# Motherboard_STM32F405RG.net
KiCad netlist of a schematic drawn in EAGLE
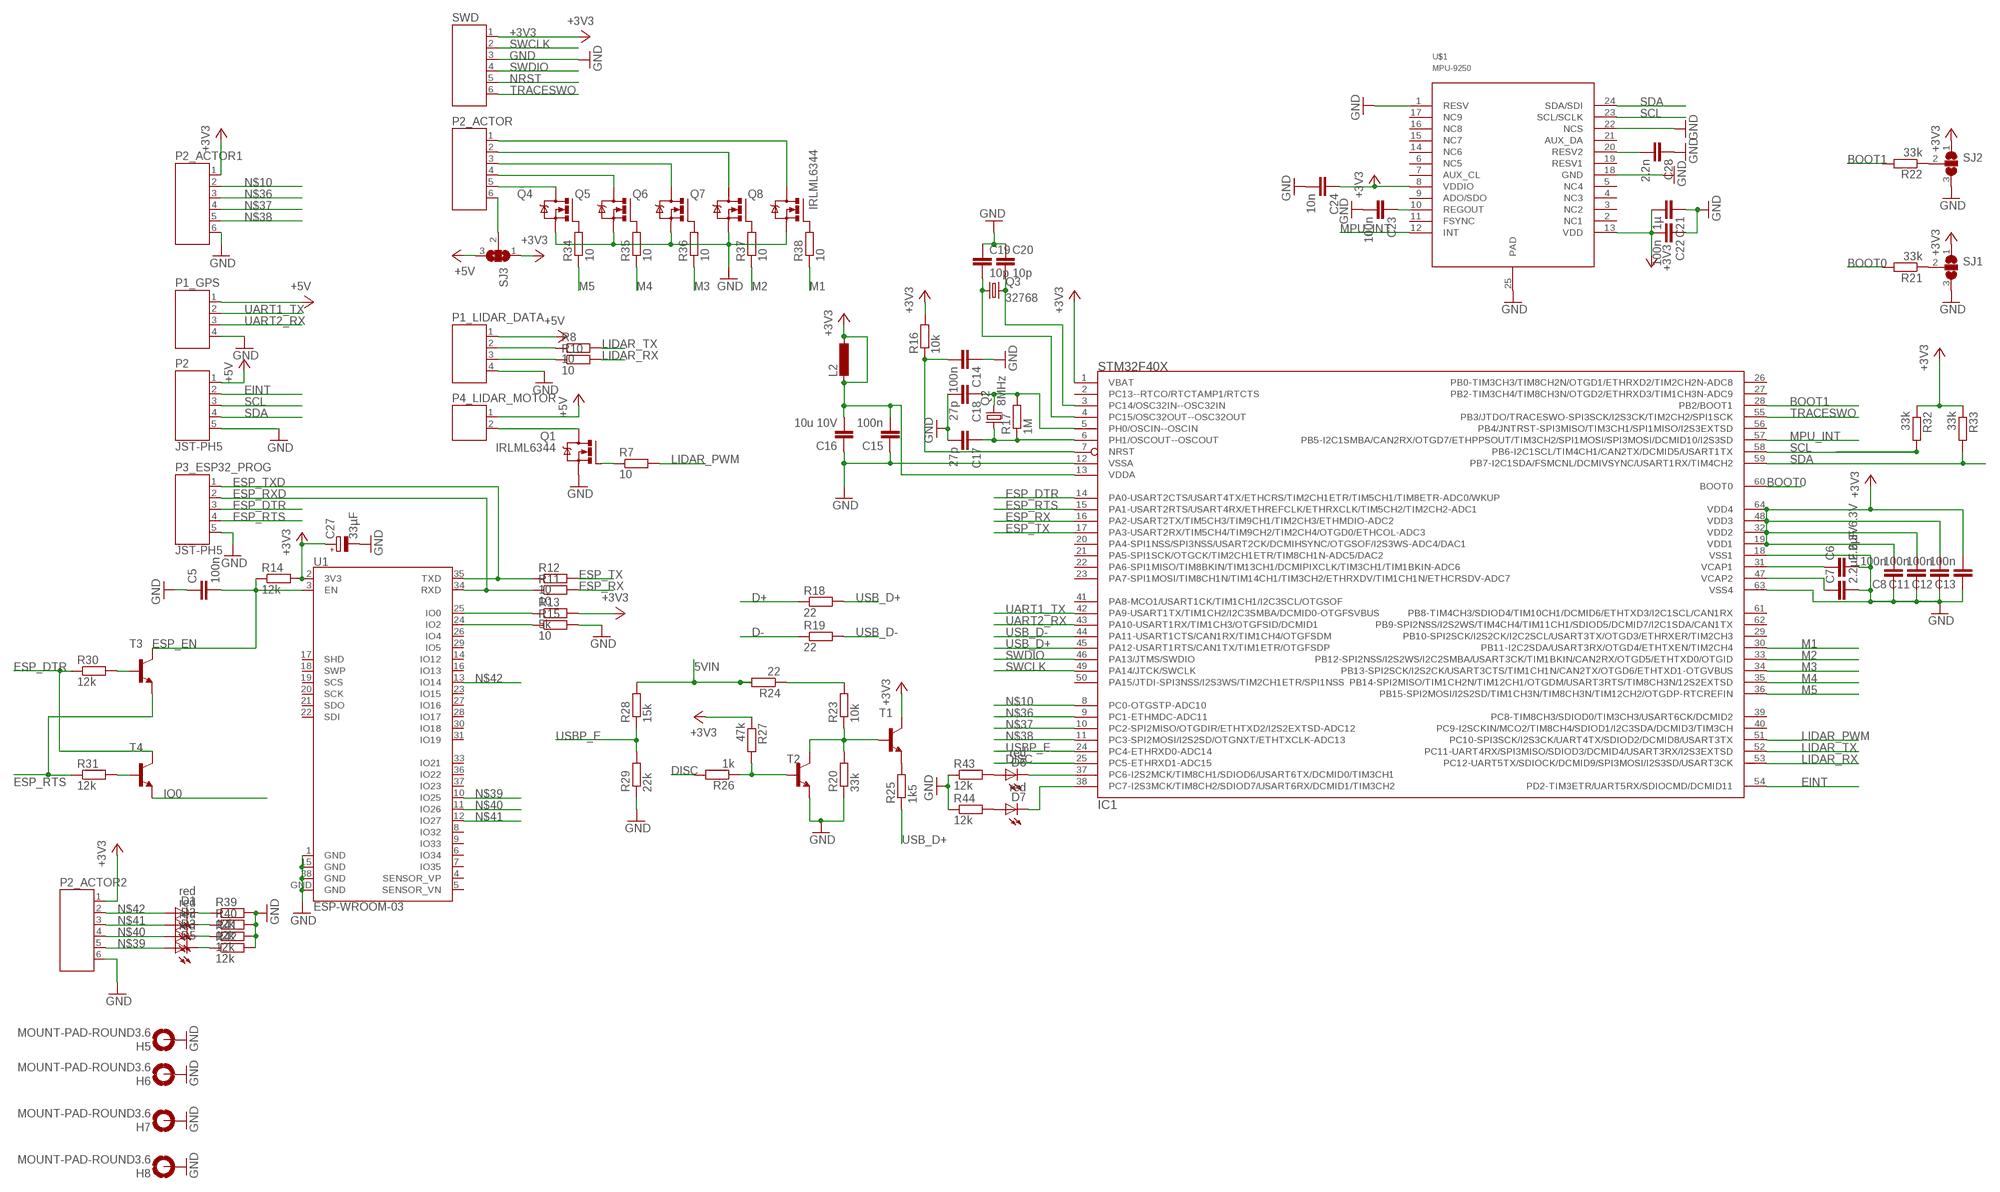
[diagram p0: schematic, sheet 1]
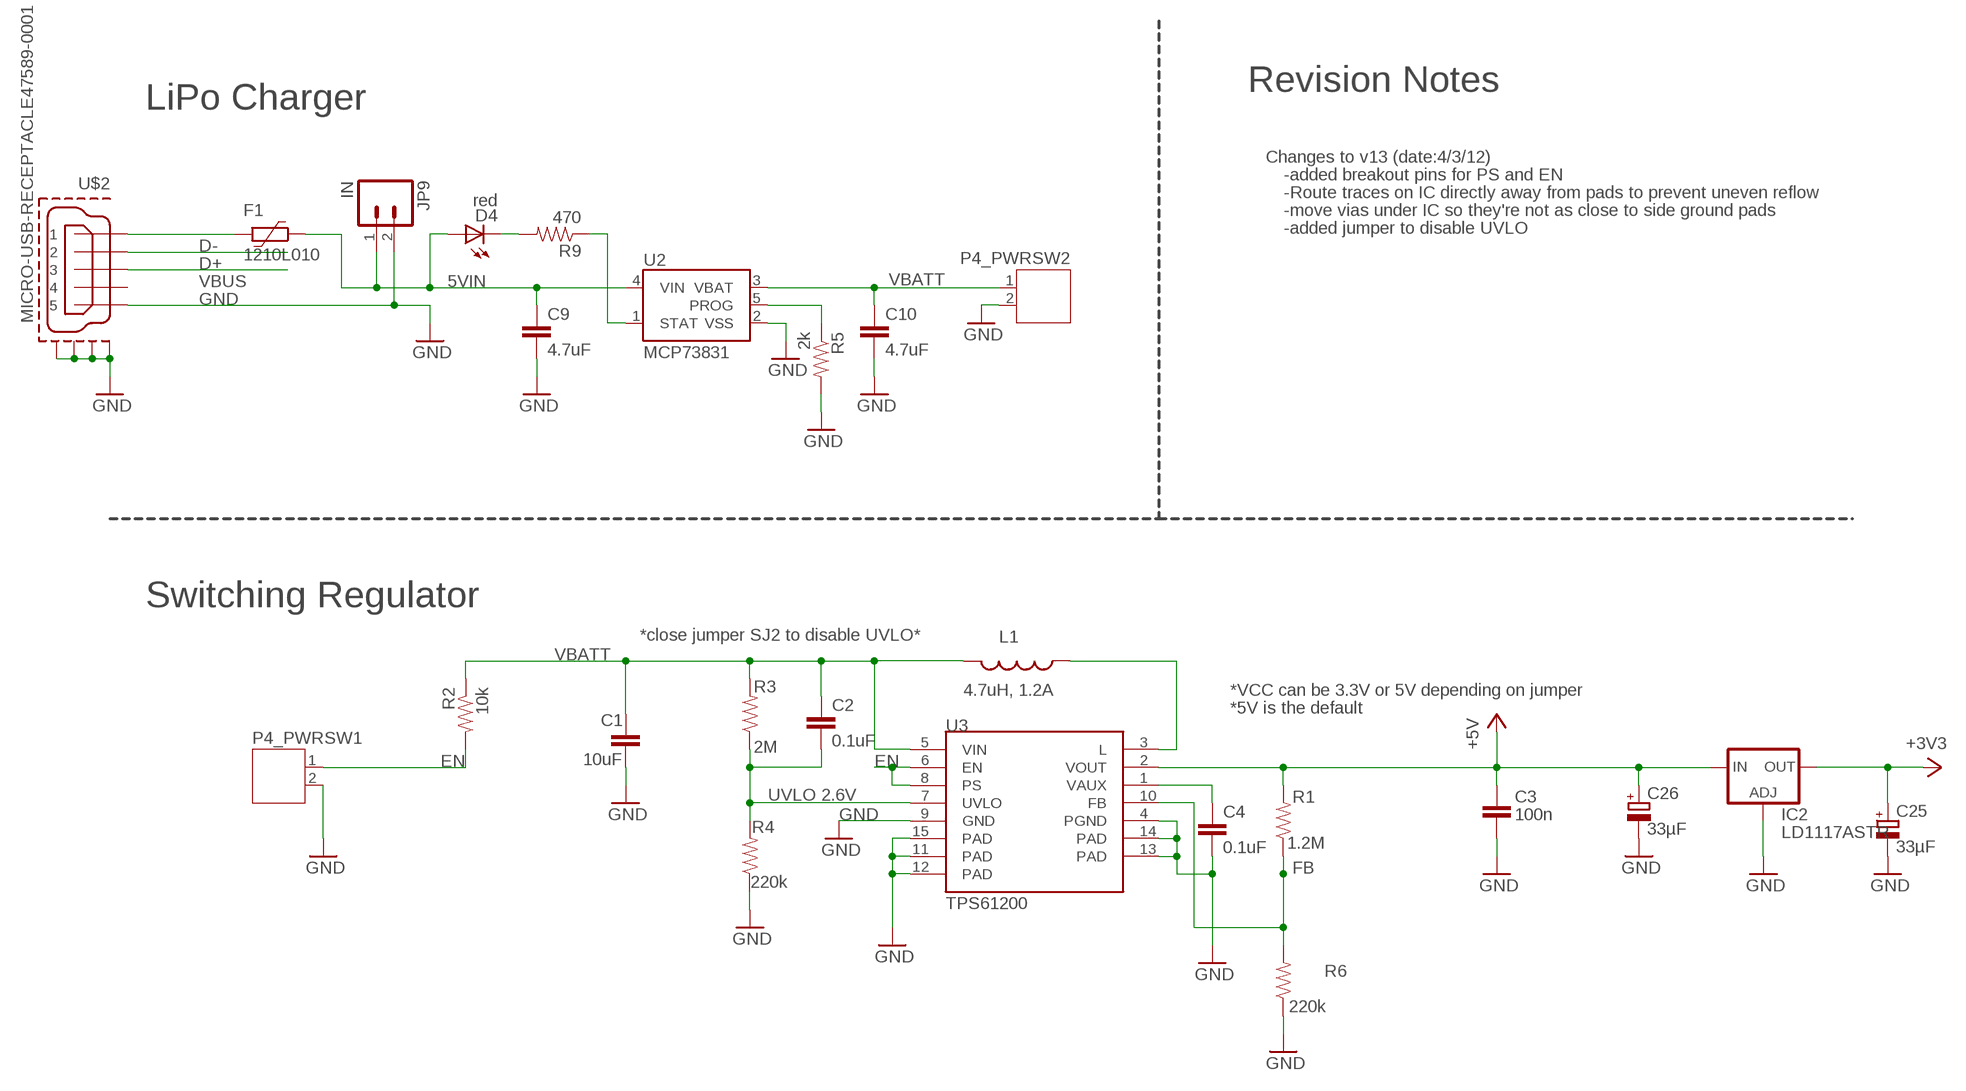
[diagram p1: schematic, sheet 2]

(export (version "E")
  (design (tool "Eeschema 10.0.6"))
  (components
    (comp (ref "C5")
      (value "100n")
      (footprint "eagle-import:C0603")
      (fields (field (name "MF") "KEMET") (field (name "MPN") "C0603C104K5RACTU"))
      (libsource (lib "eagle-import") (part "C-EUC0603"))
    )
    (comp (ref "C6")
      (value "2.2µF 6.3V")
      (footprint "eagle-import:C0603")
      (fields (field (name "MF") "KEMET") (field (name "MPN") "C0603C225K9PACTU"))
      (libsource (lib "eagle-import") (part "C-EUC0603"))
    )
    (comp (ref "C7")
      (value "2.2µF 6.3V")
      (footprint "eagle-import:C0603")
      (fields (field (name "MF") "KEMET") (field (name "MPN") "C0603C225K9PACTU"))
      (libsource (lib "eagle-import") (part "C-EUC0603"))
    )
    (comp (ref "C8")
      (value "100n")
      (footprint "eagle-import:C0603")
      (fields (field (name "MF") "KEMET") (field (name "MPN") "C0603C104K5RACTU"))
      (libsource (lib "eagle-import") (part "C-EUC0603"))
    )
    (comp (ref "C11")
      (value "100n")
      (footprint "eagle-import:C0603")
      (fields (field (name "MF") "KEMET") (field (name "MPN") "C0603C104K5RACTU"))
      (libsource (lib "eagle-import") (part "C-EUC0603"))
    )
    (comp (ref "C12")
      (value "100n")
      (footprint "eagle-import:C0603")
      (fields (field (name "MF") "KEMET") (field (name "MPN") "C0603C104K5RACTU"))
      (libsource (lib "eagle-import") (part "C-EUC0603"))
    )
    (comp (ref "C13")
      (value "100n")
      (footprint "eagle-import:C0603")
      (fields (field (name "MF") "KEMET") (field (name "MPN") "C0603C104K5RACTU"))
      (libsource (lib "eagle-import") (part "C-EUC0603"))
    )
    (comp (ref "C14")
      (value "100n")
      (footprint "eagle-import:C0603")
      (fields (field (name "MF") "KEMET") (field (name "MPN") "C0603C104K5RACTU"))
      (libsource (lib "eagle-import") (part "C-EUC0603"))
    )
    (comp (ref "C15")
      (value "100n")
      (footprint "eagle-import:C0603")
      (fields (field (name "MF") "KEMET") (field (name "MPN") "C0603C104K5RACTU"))
      (libsource (lib "eagle-import") (part "C-EUC0603"))
    )
    (comp (ref "C16")
      (value "10u 10V")
      (footprint "eagle-import:C1206")
      (fields (field (name "MF") "KEMET") (field (name "MPN") "C1206C106K8RACTU"))
      (libsource (lib "eagle-import") (part "C-EUC1206"))
    )
    (comp (ref "C17")
      (value "27p")
      (footprint "eagle-import:C0603")
      (fields (field (name "MF") "YAGEO (PHYCOMP)") (field (name "MPN") "CC0603JRNPO9BN270"))
      (libsource (lib "eagle-import") (part "C-EUC0603"))
    )
    (comp (ref "C18")
      (value "27p")
      (footprint "eagle-import:C0603")
      (fields (field (name "MF") "YAGEO (PHYCOMP)") (field (name "MPN") "CC0603JRNPO9BN270"))
      (libsource (lib "eagle-import") (part "C-EUC0603"))
    )
    (comp (ref "C19")
      (value "10p")
      (footprint "eagle-import:C0603")
      (fields (field (name "MF") "AVX") (field (name "MPN") "06035A102JAT2A"))
      (libsource (lib "eagle-import") (part "C-EUC0603"))
    )
    (comp (ref "C20")
      (value "10p")
      (footprint "eagle-import:C0603")
      (fields (field (name "MF") "AVX") (field (name "MPN") "06035A102JAT2A"))
      (libsource (lib "eagle-import") (part "C-EUC0603"))
    )
    (comp (ref "C21")
      (value "1µ")
      (footprint "eagle-import:C0603")
      (fields (field (name "MF") "AVX") (field (name "MPN") "0603YC105KAT2A"))
      (libsource (lib "eagle-import") (part "C-EUC0603"))
    )
    (comp (ref "C22")
      (value "100n")
      (footprint "eagle-import:C0603")
      (fields (field (name "MF") "KEMET") (field (name "MPN") "C0603C104K5RACTU"))
      (libsource (lib "eagle-import") (part "C-EUC0603"))
    )
    (comp (ref "C23")
      (value "100n")
      (footprint "eagle-import:C0603")
      (fields (field (name "MF") "KEMET") (field (name "MPN") "C0603C104K5RACTU"))
      (libsource (lib "eagle-import") (part "C-EUC0603"))
    )
    (comp (ref "C24")
      (value "10n")
      (footprint "eagle-import:C0603")
      (fields (field (name "MF") "YAGEO (PHYCOMP)") (field (name "MPN") "CC0603KRX7R9BB103"))
      (libsource (lib "eagle-import") (part "C-EUC0603"))
    )
    (comp (ref "C27")
      (value "33µF")
      (footprint "eagle-import:A_3216-18W")
      (fields (field (name "MF") "AVX") (field (name "MPN") "TPSA336M006R0600"))
      (libsource (lib "eagle-import") (part "CPOL-EUA/3216-18W"))
    )
    (comp (ref "C28")
      (value "2.2n")
      (footprint "eagle-import:C0603")
      (fields (field (name "MF") "YAGEO (PHYCOMP)") (field (name "MPN") "CC0603KRX7R9BB222"))
      (libsource (lib "eagle-import") (part "C-EUC0603"))
    )
    (comp (ref "D1")
      (value "red")
      (footprint "eagle-import:LED-0603")
      (fields (field (name "MF") "OSRAM") (field (name "MPN") "LSQ976-Z"))
      (libsource (lib "eagle-import") (part "LED0603"))
    )
    (comp (ref "D2")
      (value "red")
      (footprint "eagle-import:LED-0603")
      (fields (field (name "MF") "OSRAM") (field (name "MPN") "LSQ976-Z"))
      (libsource (lib "eagle-import") (part "LED0603"))
    )
    (comp (ref "D3")
      (value "red")
      (footprint "eagle-import:LED-0603")
      (fields (field (name "MF") "OSRAM") (field (name "MPN") "LSQ976-Z"))
      (libsource (lib "eagle-import") (part "LED0603"))
    )
    (comp (ref "D5")
      (value "red")
      (footprint "eagle-import:LED-0603")
      (fields (field (name "MF") "OSRAM") (field (name "MPN") "LSQ976-Z"))
      (libsource (lib "eagle-import") (part "LED0603"))
    )
    (comp (ref "D6")
      (value "red")
      (footprint "eagle-import:LED-0603")
      (fields (field (name "MF") "OSRAM") (field (name "MPN") "LSQ976-Z"))
      (libsource (lib "eagle-import") (part "LED0603"))
    )
    (comp (ref "D7")
      (value "red")
      (footprint "eagle-import:LED-0603")
      (fields (field (name "MF") "OSRAM") (field (name "MPN") "LSQ976-Z"))
      (libsource (lib "eagle-import") (part "LED0603"))
    )
    (comp (ref "H5")
      (value "MOUNT-PAD-ROUND3.6")
      (footprint "eagle-import:3,6-PAD")
      (libsource (lib "eagle-import") (part "MOUNT-PAD-ROUND3.6"))
    )
    (comp (ref "H6")
      (value "MOUNT-PAD-ROUND3.6")
      (footprint "eagle-import:3,6-PAD")
      (libsource (lib "eagle-import") (part "MOUNT-PAD-ROUND3.6"))
    )
    (comp (ref "H7")
      (value "MOUNT-PAD-ROUND3.6")
      (footprint "eagle-import:3,6-PAD")
      (libsource (lib "eagle-import") (part "MOUNT-PAD-ROUND3.6"))
    )
    (comp (ref "H8")
      (value "MOUNT-PAD-ROUND3.6")
      (footprint "eagle-import:3,6-PAD")
      (libsource (lib "eagle-import") (part "MOUNT-PAD-ROUND3.6"))
    )
    (comp (ref "IC1")
      (value "STM32F40X")
      (footprint "eagle-import:LQFP64")
      (fields (field (name "MF") "STMICROELECTRONICS") (field (name "MPN") "STM32F405RGT6"))
      (libsource (lib "eagle-import") (part "STM32F40X"))
    )
    (comp (ref "L2")
      (value "L-EUL1812")
      (footprint "eagle-import:L1812")
      (libsource (lib "eagle-import") (part "L-EUL1812"))
    )
    (comp (ref "P1_GPS")
      (value "JST-PH4")
      (footprint "eagle-import:JST-PH4")
      (fields
        (field (name "MF") "JST (JAPAN SOLDERLESS TERMINALS)")
        (field (name "MPN") "B4B-PH-K-S(LF)(SN)")
      )
      (libsource (lib "eagle-import") (part "JST-PH4"))
    )
    (comp (ref "P1_LIDAR_DATA")
      (value "JST-PH4")
      (footprint "eagle-import:JST-PH4")
      (fields
        (field (name "MF") "JST (JAPAN SOLDERLESS TERMINALS)")
        (field (name "MPN") "B4B-PH-K-S(LF)(SN)")
      )
      (libsource (lib "eagle-import") (part "JST-PH4"))
    )
    (comp (ref "P2")
      (value "JST-PH5")
      (footprint "eagle-import:JST-PH5")
      (fields
        (field (name "MF") "JST (JAPAN SOLDERLESS TERMINALS)")
        (field (name "MPN") "B5B-PH-K-S(LF)(SN)")
      )
      (libsource (lib "eagle-import") (part "JST-PH5"))
    )
    (comp (ref "P2_ACTOR")
      (value "JST-PH6")
      (footprint "eagle-import:JST-PH6")
      (fields
        (field (name "MF") "JST (JAPAN SOLDERLESS TERMINALS)")
        (field (name "MPN") "B6B-PH-K-S(LF)(SN)")
      )
      (libsource (lib "eagle-import") (part "JST-PH6"))
    )
    (comp (ref "P2_ACTOR1")
      (value "JST-PH6")
      (footprint "eagle-import:JST-PH6")
      (fields
        (field (name "MF") "JST (JAPAN SOLDERLESS TERMINALS)")
        (field (name "MPN") "B6B-PH-K-S(LF)(SN)")
      )
      (libsource (lib "eagle-import") (part "JST-PH6"))
    )
    (comp (ref "P2_ACTOR2")
      (value "JST-PH6")
      (footprint "eagle-import:JST-PH6")
      (fields
        (field (name "MF") "JST (JAPAN SOLDERLESS TERMINALS)")
        (field (name "MPN") "B6B-PH-K-S(LF)(SN)")
      )
      (libsource (lib "eagle-import") (part "JST-PH6"))
    )
    (comp (ref "P3_ESP32_PROG")
      (value "JST-PH5")
      (footprint "eagle-import:JST-PH5")
      (fields
        (field (name "MF") "JST (JAPAN SOLDERLESS TERMINALS)")
        (field (name "MPN") "B5B-PH-K-S(LF)(SN)")
      )
      (libsource (lib "eagle-import") (part "JST-PH5"))
    )
    (comp (ref "P4_LIDAR_MOTOR")
      (value "JST-PH2")
      (footprint "eagle-import:JST-PH2")
      (fields
        (field (name "MF") "JST (JAPAN SOLDERLESS TERMINALS)")
        (field (name "MPN") "B2B-PH-K-S(LF)(SN)")
      )
      (libsource (lib "eagle-import") (part "JST-PH2"))
    )
    (comp (ref "Q1")
      (value "IRLML6344")
      (footprint "eagle-import:SOT23")
      (fields (field (name "MF") "INFINEON") (field (name "MPN") "IRLML6344TRPBF"))
      (libsource (lib "eagle-import") (part "IRLML6344"))
    )
    (comp (ref "Q2")
      (value "8MHz")
      (footprint "eagle-import:HC18U-V")
      (fields
        (field (name "MF") "MULTICOMP")
        (field (name "MPN") "HC49S-8-30-50-70-30-ATF")
        (field (name "OC_FARNELL") "1666997")
      )
      (libsource (lib "eagle-import") (part "CRYSTALHC18U-V"))
    )
    (comp (ref "Q3")
      (value "32768")
      (footprint "eagle-import:TC38H")
      (fields
        (field (name "MF") "CITIZEN FINETECH MIYOTA")
        (field (name "MPN") "CFS206 32.768KDZB-UB")
        (field (name "OC_FARNELL") "1457085")
      )
      (libsource (lib "eagle-import") (part "CRYSTALTC38H"))
    )
    (comp (ref "Q4")
      (value "IRLML6344")
      (footprint "eagle-import:SOT23")
      (fields (field (name "MF") "INFINEON") (field (name "MPN") "IRLML6344TRPBF"))
      (libsource (lib "eagle-import") (part "IRLML6344"))
    )
    (comp (ref "Q5")
      (value "IRLML6344")
      (footprint "eagle-import:SOT23")
      (fields (field (name "MF") "INFINEON") (field (name "MPN") "IRLML6344TRPBF"))
      (libsource (lib "eagle-import") (part "IRLML6344"))
    )
    (comp (ref "Q6")
      (value "IRLML6344")
      (footprint "eagle-import:SOT23")
      (fields (field (name "MF") "INFINEON") (field (name "MPN") "IRLML6344TRPBF"))
      (libsource (lib "eagle-import") (part "IRLML6344"))
    )
    (comp (ref "Q7")
      (value "IRLML6344")
      (footprint "eagle-import:SOT23")
      (fields (field (name "MF") "INFINEON") (field (name "MPN") "IRLML6344TRPBF"))
      (libsource (lib "eagle-import") (part "IRLML6344"))
    )
    (comp (ref "Q8")
      (value "IRLML6344")
      (footprint "eagle-import:SOT23")
      (fields (field (name "MF") "INFINEON") (field (name "MPN") "IRLML6344TRPBF"))
      (libsource (lib "eagle-import") (part "IRLML6344"))
    )
    (comp (ref "R7")
      (value "10")
      (footprint "eagle-import:R0603")
      (fields (field (name "MF") "VISHAY") (field (name "MPN") "CRCW060310R0FKEA"))
      (libsource (lib "eagle-import") (part "R-EU_R0603"))
    )
    (comp (ref "R8")
      (value "10")
      (footprint "eagle-import:R0603")
      (fields (field (name "MF") "VISHAY") (field (name "MPN") "CRCW060310R0FKEA"))
      (libsource (lib "eagle-import") (part "R-EU_R0603"))
    )
    (comp (ref "R10")
      (value "10")
      (footprint "eagle-import:R0603")
      (fields (field (name "MF") "VISHAY") (field (name "MPN") "CRCW060310R0FKEA"))
      (libsource (lib "eagle-import") (part "R-EU_R0603"))
    )
    (comp (ref "R11")
      (value "10")
      (footprint "eagle-import:R0603")
      (fields (field (name "MF") "VISHAY") (field (name "MPN") "CRCW060310R0FKEA"))
      (libsource (lib "eagle-import") (part "R-EU_R0603"))
    )
    (comp (ref "R12")
      (value "10")
      (footprint "eagle-import:R0603")
      (fields (field (name "MF") "VISHAY") (field (name "MPN") "CRCW060310R0FKEA"))
      (libsource (lib "eagle-import") (part "R-EU_R0603"))
    )
    (comp (ref "R13")
      (value "5k")
      (footprint "eagle-import:R0603")
      (fields (field (name "MF") "VISHAY") (field (name "MPN") "CRCW060310R0FKEA"))
      (libsource (lib "eagle-import") (part "R-EU_R0603"))
    )
    (comp (ref "R14")
      (value "12k")
      (footprint "eagle-import:R0603")
      (fields (field (name "MF") "VISHAY") (field (name "MPN") "CRCW060310R0FKEA"))
      (libsource (lib "eagle-import") (part "R-EU_R0603"))
    )
    (comp (ref "R15")
      (value "10")
      (footprint "eagle-import:R0603")
      (fields (field (name "MF") "VISHAY") (field (name "MPN") "CRCW060310R0FKEA"))
      (libsource (lib "eagle-import") (part "R-EU_R0603"))
    )
    (comp (ref "R16")
      (value "10k")
      (footprint "eagle-import:R0603")
      (fields (field (name "MF") "VISHAY") (field (name "MPN") "CRCW060310R0FKEA"))
      (libsource (lib "eagle-import") (part "R-EU_R0603"))
    )
    (comp (ref "R17")
      (value "1M")
      (footprint "eagle-import:R0603")
      (fields (field (name "MF") "VISHAY") (field (name "MPN") "CRCW06031M00FKEA"))
      (libsource (lib "eagle-import") (part "R-EU_R0603"))
    )
    (comp (ref "R18")
      (value "22")
      (footprint "eagle-import:R0603")
      (fields (field (name "MF") "VISHAY") (field (name "MPN") "CRCW060322R0FKEA"))
      (libsource (lib "eagle-import") (part "R-EU_R0603"))
    )
    (comp (ref "R19")
      (value "22")
      (footprint "eagle-import:R0603")
      (fields (field (name "MF") "VISHAY") (field (name "MPN") "CRCW060322R0FKEA"))
      (libsource (lib "eagle-import") (part "R-EU_R0603"))
    )
    (comp (ref "R20")
      (value "33k")
      (footprint "eagle-import:R0603")
      (fields (field (name "MF") "VISHAY") (field (name "MPN") "CRCW060333K0FKEA"))
      (libsource (lib "eagle-import") (part "R-EU_R0603"))
    )
    (comp (ref "R21")
      (value "33k")
      (footprint "eagle-import:R0603")
      (fields (field (name "MF") "VISHAY") (field (name "MPN") "CRCW060333K0FKEA"))
      (libsource (lib "eagle-import") (part "R-EU_R0603"))
    )
    (comp (ref "R22")
      (value "33k")
      (footprint "eagle-import:R0603")
      (fields (field (name "MF") "VISHAY") (field (name "MPN") "CRCW060333K0FKEA"))
      (libsource (lib "eagle-import") (part "R-EU_R0603"))
    )
    (comp (ref "R23")
      (value "10k")
      (footprint "eagle-import:R0603")
      (fields (field (name "MF") "MULTICOMP") (field (name "MPN") "MCMR06X1002FTL"))
      (libsource (lib "eagle-import") (part "R-EU_R0603"))
    )
    (comp (ref "R24")
      (value "22")
      (footprint "eagle-import:R0603")
      (fields (field (name "MF") "VISHAY") (field (name "MPN") "CRCW060322R0FKEA"))
      (libsource (lib "eagle-import") (part "R-EU_R0603"))
    )
    (comp (ref "R25")
      (value "1k5")
      (footprint "eagle-import:R0603")
      (fields (field (name "MF") "MULTICOMP") (field (name "MPN") "MCMR06X1501FTL"))
      (libsource (lib "eagle-import") (part "R-EU_R0603"))
    )
    (comp (ref "R26")
      (value "1k")
      (footprint "eagle-import:R0603")
      (fields (field (name "MF") "VISHAY") (field (name "MPN") "CRCW06031K00FKEA"))
      (libsource (lib "eagle-import") (part "R-EU_R0603"))
    )
    (comp (ref "R27")
      (value "47k")
      (footprint "eagle-import:R0603")
      (fields (field (name "MF") "VISHAY") (field (name "MPN") "CRCW060347K0FKEA"))
      (libsource (lib "eagle-import") (part "R-EU_R0603"))
    )
    (comp (ref "R28")
      (value "15k")
      (footprint "eagle-import:R0603")
      (fields (field (name "MF") "VISHAY") (field (name "MPN") "CRCW060315K0FKEA"))
      (libsource (lib "eagle-import") (part "R-EU_R0603"))
    )
    (comp (ref "R29")
      (value "22k")
      (footprint "eagle-import:R0603")
      (fields (field (name "MF") "TE CONNECTIVITY / NEOHM") (field (name "MPN") "CPF0603F4K22C1"))
      (libsource (lib "eagle-import") (part "R-EU_R0603"))
    )
    (comp (ref "R30")
      (value "12k")
      (footprint "eagle-import:R0603")
      (fields (field (name "MF") "MULTICOMP") (field (name "MPN") "MC0063W060312K8"))
      (libsource (lib "eagle-import") (part "R-EU_R0603"))
    )
    (comp (ref "R31")
      (value "12k")
      (footprint "eagle-import:R0603")
      (fields (field (name "MF") "MULTICOMP") (field (name "MPN") "MC0063W060312K8"))
      (libsource (lib "eagle-import") (part "R-EU_R0603"))
    )
    (comp (ref "R32")
      (value "33k")
      (footprint "eagle-import:R0603")
      (fields (field (name "MF") "VISHAY") (field (name "MPN") "CRCW060333K0FKEA"))
      (libsource (lib "eagle-import") (part "R-EU_R0603"))
    )
    (comp (ref "R33")
      (value "33k")
      (footprint "eagle-import:R0603")
      (fields (field (name "MF") "VISHAY") (field (name "MPN") "CRCW060333K0FKEA"))
      (libsource (lib "eagle-import") (part "R-EU_R0603"))
    )
    (comp (ref "R34")
      (value "10")
      (footprint "eagle-import:R0603")
      (fields (field (name "MF") "VISHAY") (field (name "MPN") "CRCW060310R0FKEA"))
      (libsource (lib "eagle-import") (part "R-EU_R0603"))
    )
    (comp (ref "R35")
      (value "10")
      (footprint "eagle-import:R0603")
      (fields (field (name "MF") "VISHAY") (field (name "MPN") "CRCW060310R0FKEA"))
      (libsource (lib "eagle-import") (part "R-EU_R0603"))
    )
    (comp (ref "R36")
      (value "10")
      (footprint "eagle-import:R0603")
      (fields (field (name "MF") "VISHAY") (field (name "MPN") "CRCW060310R0FKEA"))
      (libsource (lib "eagle-import") (part "R-EU_R0603"))
    )
    (comp (ref "R37")
      (value "10")
      (footprint "eagle-import:R0603")
      (fields (field (name "MF") "VISHAY") (field (name "MPN") "CRCW060310R0FKEA"))
      (libsource (lib "eagle-import") (part "R-EU_R0603"))
    )
    (comp (ref "R38")
      (value "10")
      (footprint "eagle-import:R0603")
      (fields (field (name "MF") "VISHAY") (field (name "MPN") "CRCW060310R0FKEA"))
      (libsource (lib "eagle-import") (part "R-EU_R0603"))
    )
    (comp (ref "R39")
      (value "12k")
      (footprint "eagle-import:R0603")
      (fields (field (name "MF") "MULTICOMP") (field (name "MPN") "MC0063W060312K8"))
      (libsource (lib "eagle-import") (part "R-EU_R0603"))
    )
    (comp (ref "R40")
      (value "12k")
      (footprint "eagle-import:R0603")
      (fields (field (name "MF") "MULTICOMP") (field (name "MPN") "MC0063W060312K8"))
      (libsource (lib "eagle-import") (part "R-EU_R0603"))
    )
    (comp (ref "R41")
      (value "12k")
      (footprint "eagle-import:R0603")
      (fields (field (name "MF") "MULTICOMP") (field (name "MPN") "MC0063W060312K8"))
      (libsource (lib "eagle-import") (part "R-EU_R0603"))
    )
    (comp (ref "R42")
      (value "12k")
      (footprint "eagle-import:R0603")
      (fields (field (name "MF") "MULTICOMP") (field (name "MPN") "MC0063W060312K8"))
      (libsource (lib "eagle-import") (part "R-EU_R0603"))
    )
    (comp (ref "R43")
      (value "12k")
      (footprint "eagle-import:R0603")
      (fields (field (name "MF") "MULTICOMP") (field (name "MPN") "MC0063W060312K8"))
      (libsource (lib "eagle-import") (part "R-EU_R0603"))
    )
    (comp (ref "R44")
      (value "12k")
      (footprint "eagle-import:R0603")
      (fields (field (name "MF") "MULTICOMP") (field (name "MPN") "MC0063W060312K8"))
      (libsource (lib "eagle-import") (part "R-EU_R0603"))
    )
    (comp (ref "SJ1")
      (value "SJ2W")
      (footprint "eagle-import:SJ_2")
      (libsource (lib "eagle-import") (part "SJ2W"))
    )
    (comp (ref "SJ2")
      (value "SJ2W")
      (footprint "eagle-import:SJ_2")
      (libsource (lib "eagle-import") (part "SJ2W"))
    )
    (comp (ref "SJ3")
      (value "SJ2W")
      (footprint "eagle-import:SJ_2")
      (libsource (lib "eagle-import") (part "SJ2W"))
    )
    (comp (ref "SWD")
      (value "JST-PH6")
      (footprint "eagle-import:JST-PH6")
      (fields
        (field (name "MF") "JST (JAPAN SOLDERLESS TERMINALS)")
        (field (name "MPN") "B6B-PH-K-S(LF)(SN)")
      )
      (libsource (lib "eagle-import") (part "JST-PH6"))
    )
    (comp (ref "T1")
      (value "BC817-16-NPN-SOT23-BEC")
      (footprint "eagle-import:SOT23-BEC")
      (fields (field (name "MF") "NEXPERIA") (field (name "MPN") "BC817,215"))
      (libsource (lib "eagle-import") (part "-NPN-SOT23-BECBC817-16"))
    )
    (comp (ref "T2")
      (value "BC817-16-NPN-SOT23-BEC")
      (footprint "eagle-import:SOT23-BEC")
      (fields (field (name "MF") "NEXPERIA") (field (name "MPN") "BC817,215"))
      (libsource (lib "eagle-import") (part "-NPN-SOT23-BECBC817-16"))
    )
    (comp (ref "T3")
      (value "BC817-16-NPN-SOT23-BEC")
      (footprint "eagle-import:SOT23-BEC")
      (fields (field (name "MF") "NEXPERIA") (field (name "MPN") "BC817,215"))
      (libsource (lib "eagle-import") (part "-NPN-SOT23-BECBC817-16"))
    )
    (comp (ref "T4")
      (value "BC817-16-NPN-SOT23-BEC")
      (footprint "eagle-import:SOT23-BEC")
      (fields (field (name "MF") "NEXPERIA") (field (name "MPN") "BC817,215"))
      (libsource (lib "eagle-import") (part "-NPN-SOT23-BECBC817-16"))
    )
    (comp (ref "U$1")
      (value "MPU-9250")
      (footprint "eagle-import:LEAD-QFN24")
      (fields (field (name "MF") "INVENSENSE") (field (name "MPN") "MPU-6050"))
      (libsource (lib "eagle-import") (part "MPU-9250"))
    )
    (comp (ref "U1")
      (value "ESP-WROOM-03")
      (footprint "eagle-import:ESP-WROOM-03")
      (libsource (lib "eagle-import") (part "ESP-WROOM-03"))
    )
    (comp (ref "C1")
      (value "10uF")
      (footprint "eagle-import:1206")
      (fields (field (name "MF") "KEMET") (field (name "MPN") "C1206C106K8RACTU"))
      (libsource (lib "eagle-import") (part "CAP1206"))
    )
    (comp (ref "C2")
      (value "0.1uF")
      (footprint "eagle-import:0603-CAP")
      (fields (field (name "MF") "YAGEO (PHYCOMP)") (field (name "MPN") "CC0603MRY5V9BB104"))
      (libsource (lib "eagle-import") (part "CAP0603-CAP"))
    )
    (comp (ref "C3")
      (value "100n")
      (footprint "eagle-import:0805")
      (fields (field (name "MF") "KEMET") (field (name "MPN") "C0603C104K5RACTU"))
      (libsource (lib "eagle-import") (part "CAP0805"))
    )
    (comp (ref "C4")
      (value "0.1uF")
      (footprint "eagle-import:0603-CAP")
      (fields (field (name "MF") "YAGEO (PHYCOMP)") (field (name "MPN") "CC0603MRY5V9BB104"))
      (libsource (lib "eagle-import") (part "CAP0603-CAP"))
    )
    (comp (ref "C9")
      (value "4.7uF")
      (footprint "eagle-import:0603-CAP")
      (fields (field (name "MF") "KEMET") (field (name "MPN") "C0603C475K8PACTU"))
      (libsource (lib "eagle-import") (part "CAP0603-CAP"))
    )
    (comp (ref "C10")
      (value "4.7uF")
      (footprint "eagle-import:0603-CAP")
      (fields (field (name "MF") "KEMET") (field (name "MPN") "C0603C475K8PACTU"))
      (libsource (lib "eagle-import") (part "CAP0603-CAP"))
    )
    (comp (ref "C25")
      (value "33µF")
      (footprint "eagle-import:A_3216-18W")
      (fields (field (name "MF") "AVX") (field (name "MPN") "TPSA336M006R0600"))
      (libsource (lib "eagle-import") (part "CPOL-EUA/3216-18W"))
    )
    (comp (ref "C26")
      (value "33µF")
      (footprint "eagle-import:A_3216-18W")
      (fields (field (name "MF") "AVX") (field (name "MPN") "TPSA336M006R0600"))
      (libsource (lib "eagle-import") (part "CPOL-EUA/3216-18W"))
    )
    (comp (ref "D4")
      (value "red")
      (footprint "eagle-import:LED-0603")
      (fields (field (name "MF") "OSRAM") (field (name "MPN") "LSQ976-Z"))
      (libsource (lib "eagle-import") (part "LED0603"))
    )
    (comp (ref "F1")
      (value "1210L010")
      (footprint "eagle-import:1210L")
      (fields
        (field (name "MF") "Littelfuse")
        (field (name "MF_1") "LITTELFUSE")
        (field (name "MPN") "1210L010WR")
      )
      (libsource (lib "eagle-import") (part "?1210L010"))
    )
    (comp (ref "IC2")
      (value "LD1117ASTR")
      (footprint "eagle-import:SOT223")
      (fields (field (name "MF") "ON SEMICONDUCTOR") (field (name "MPN") "NCP1117ST33T3G"))
      (libsource (lib "eagle-import") (part "LD117A?STR"))
    )
    (comp (ref "JP9")
      (value "IN")
      (footprint "eagle-import:1X02")
      (fields
        (field (name "MF") "JST (JAPAN SOLDERLESS TERMINALS)")
        (field (name "MPN") "B2B-PH-K-S(LF)(SN)")
      )
      (libsource (lib "eagle-import") (part "M02PTH"))
    )
    (comp (ref "L1")
      (value "4.7uH, 1.2A")
      (footprint "eagle-import:CDRH2D09")
      (fields (field (name "MF") "MURATA") (field (name "MPN") "LQH3NPN4R7MJ0L"))
      (libsource (lib "eagle-import") (part "INDUCTOR."))
    )
    (comp (ref "P4_PWRSW1")
      (value "JST-PH2")
      (footprint "eagle-import:JST-PH2")
      (fields
        (field (name "MF") "JST (JAPAN SOLDERLESS TERMINALS)")
        (field (name "MPN") "B2B-PH-K-S(LF)(SN)")
      )
      (libsource (lib "eagle-import") (part "JST-PH2"))
    )
    (comp (ref "P4_PWRSW2")
      (value "JST-PH2")
      (footprint "eagle-import:JST-PH2")
      (fields
        (field (name "MF") "JST (JAPAN SOLDERLESS TERMINALS)")
        (field (name "MPN") "B2B-PH-K-S(LF)(SN)")
      )
      (libsource (lib "eagle-import") (part "JST-PH2"))
    )
    (comp (ref "R1")
      (value "1.2M")
      (footprint "eagle-import:0603-RES")
      (fields (field (name "MF") "MULTICOMP") (field (name "MPN") "MCMR06W2004FTL"))
      (libsource (lib "eagle-import") (part "RESISTOR0603-RES"))
    )
    (comp (ref "R2")
      (value "10k")
      (footprint "eagle-import:0603-RES")
      (fields (field (name "MF") "MULTICOMP") (field (name "MPN") "MCMR06X1002FTL"))
      (libsource (lib "eagle-import") (part "RESISTOR0603-RES"))
    )
    (comp (ref "R3")
      (value "2M")
      (footprint "eagle-import:0603-RES")
      (fields (field (name "MF") "KOA SPEER ELECTRONICS") (field (name "MPN") "RK73H1JTTD1204F"))
      (libsource (lib "eagle-import") (part "RESISTOR0603-RES"))
    )
    (comp (ref "R4")
      (value "220k")
      (footprint "eagle-import:0603-RES")
      (fields (field (name "MF") "MULTICOMP") (field (name "MPN") "MCHP03W8F2203T5E"))
      (libsource (lib "eagle-import") (part "RESISTOR0603-RES"))
    )
    (comp (ref "R5")
      (value "2k")
      (footprint "eagle-import:0603-RES")
      (fields (field (name "MF") "YAGEO (PHYCOMP)") (field (name "MPN") "RC0603FR-072K2L."))
      (libsource (lib "eagle-import") (part "RESISTOR0603-RES"))
    )
    (comp (ref "R6")
      (value "220k")
      (footprint "eagle-import:0603-RES")
      (fields (field (name "MF") "MULTICOMP") (field (name "MPN") "MCHP03W8F2203T5E"))
      (libsource (lib "eagle-import") (part "RESISTOR0603-RES"))
    )
    (comp (ref "R9")
      (value "470")
      (footprint "eagle-import:0603-RES")
      (fields (field (name "MF") "MULTICOMP") (field (name "MPN") "MCHP03W8F4700T5E"))
      (libsource (lib "eagle-import") (part "RESISTOR0603-RES"))
    )
    (comp (ref "U$2")
      (value "MICRO-USB-RECEPTACLE47589-0001")
      (footprint "eagle-import:47589-0001")
      (fields (field (name "MF") "MOLEX") (field (name "MPN") "47589-0001"))
      (libsource (lib "eagle-import") (part "MICRO-USB-RECEPTACLE47589-0001"))
    )
    (comp (ref "U2")
      (value "MCP73831")
      (footprint "eagle-import:SOT23-5")
      (fields (field (name "MF") "MICROCHIP") (field (name "MPN") "MCP73831T-2ACI/OT"))
      (libsource (lib "eagle-import") (part "MCP73831"))
    )
    (comp (ref "U3")
      (value "TPS61200")
      (footprint "eagle-import:QFN-10_PAD")
      (fields (field (name "MF") "TEXAS INSTRUMENTS") (field (name "MPN") "TPS61200DRCT"))
      (libsource (lib "eagle-import") (part "TPS61200"))
    )
  )
  (nets
    (net (code "1") (name "+3V3") (class "Default")
      (node (ref "C11") (pin "2") (pinfunction "2_2") (pintype "passive"))
      (node (ref "C12") (pin "2") (pinfunction "2_2") (pintype "passive"))
      (node (ref "C13") (pin "2") (pinfunction "2_2") (pintype "passive"))
      (node (ref "C15") (pin "2") (pinfunction "2_2") (pintype "passive"))
      (node (ref "C16") (pin "2") (pinfunction "2_2") (pintype "passive"))
      (node (ref "C21") (pin "2") (pinfunction "2_2") (pintype "passive"))
      (node (ref "C22") (pin "2") (pinfunction "2_2") (pintype "passive"))
      (node (ref "C24") (pin "1") (pinfunction "1_1") (pintype "passive"))
      (node (ref "C25") (pin "+") (pinfunction "+_+") (pintype "passive"))
      (node (ref "C27") (pin "+") (pinfunction "+_+") (pintype "passive"))
      (node (ref "C8") (pin "2") (pinfunction "2_2") (pintype "passive"))
      (node (ref "IC1") (pin "1") (pinfunction "VBAT_1") (pintype "power_in"))
      (node (ref "IC1") (pin "13") (pinfunction "VDDA_13") (pintype "power_in"))
      (node (ref "IC1") (pin "19") (pinfunction "VDD1_19") (pintype "power_in"))
      (node (ref "IC1") (pin "32") (pinfunction "VDD2_32") (pintype "power_in"))
      (node (ref "IC1") (pin "48") (pinfunction "VDD3_48") (pintype "power_in"))
      (node (ref "IC1") (pin "64") (pinfunction "VDD4_64") (pintype "bidirectional"))
      (node (ref "IC2") (pin "2") (pinfunction "OUT_2") (pintype "passive"))
      (node (ref "IC2") (pin "4") (pinfunction "OUT_4") (pintype "passive"))
      (node (ref "L2") (pin "1") (pinfunction "1_1") (pintype "passive"))
      (node (ref "L2") (pin "2") (pinfunction "2_2") (pintype "passive"))
      (node (ref "P2_ACTOR1") (pin "1") (pinfunction "1_1") (pintype "passive"))
      (node (ref "P2_ACTOR2") (pin "1") (pinfunction "1_1") (pintype "passive"))
      (node (ref "R13") (pin "2") (pinfunction "2_2") (pintype "passive"))
      (node (ref "R14") (pin "2") (pinfunction "2_2") (pintype "passive"))
      (node (ref "R16") (pin "2") (pinfunction "2_2") (pintype "passive"))
      (node (ref "R27") (pin "1") (pinfunction "1_1") (pintype "passive"))
      (node (ref "R32") (pin "1") (pinfunction "1_1") (pintype "passive"))
      (node (ref "R33") (pin "1") (pinfunction "1_1") (pintype "passive"))
      (node (ref "SJ1") (pin "1") (pinfunction "1_1") (pintype "passive"))
      (node (ref "SJ2") (pin "1") (pinfunction "1_1") (pintype "passive"))
      (node (ref "SJ3") (pin "1") (pinfunction "1_1") (pintype "passive"))
      (node (ref "SWD") (pin "1") (pinfunction "1_1") (pintype "passive"))
      (node (ref "T1") (pin "C") (pinfunction "C_C") (pintype "passive"))
      (node (ref "U$1") (pin "13") (pinfunction "VDD_13") (pintype "bidirectional"))
      (node (ref "U$1") (pin "8") (pinfunction "VDDIO_8") (pintype "bidirectional"))
      (node (ref "U1") (pin "2") (pinfunction "3V3_2") (pintype "bidirectional"))
    )
    (net (code "2") (name "+5V") (class "Default")
      (node (ref "C26") (pin "+") (pinfunction "+_+") (pintype "passive"))
      (node (ref "C3") (pin "1") (pinfunction "1_1") (pintype "passive"))
      (node (ref "IC2") (pin "3") (pinfunction "IN_3") (pintype "input"))
      (node (ref "P1_GPS") (pin "1") (pinfunction "1_1") (pintype "passive"))
      (node (ref "P1_LIDAR_DATA") (pin "1") (pinfunction "1_1") (pintype "passive"))
      (node (ref "P2") (pin "1") (pinfunction "1_1") (pintype "passive"))
      (node (ref "P4_LIDAR_MOTOR") (pin "1") (pinfunction "1_1") (pintype "passive"))
      (node (ref "R1") (pin "2") (pinfunction "2_2") (pintype "passive"))
      (node (ref "SJ3") (pin "3") (pinfunction "3_3") (pintype "passive"))
      (node (ref "U3") (pin "2") (pinfunction "VOUT_2") (pintype "passive"))
    )
    (net (code "3") (name "5VIN") (class "Default")
      (node (ref "C9") (pin "1") (pinfunction "1_1") (pintype "passive"))
      (node (ref "D4") (pin "A") (pinfunction "A_A") (pintype "passive"))
      (node (ref "F1") (pin "1") (pinfunction "1_1") (pintype "passive"))
      (node (ref "JP9") (pin "1") (pinfunction "1_1") (pintype "passive"))
      (node (ref "R24") (pin "2") (pinfunction "2_2") (pintype "passive"))
      (node (ref "R28") (pin "2") (pinfunction "2_2") (pintype "passive"))
      (node (ref "U2") (pin "4") (pinfunction "VIN_4") (pintype "power_in"))
    )
    (net (code "4") (name "BOOT0") (class "Default")
      (node (ref "IC1") (pin "60") (pinfunction "BOOT0_60") (pintype "input"))
      (node (ref "R21") (pin "2") (pinfunction "2_2") (pintype "passive"))
    )
    (net (code "5") (name "BOOT1") (class "Default")
      (node (ref "IC1") (pin "28") (pinfunction "PB2/BOOT1_28") (pintype "bidirectional"))
      (node (ref "R22") (pin "2") (pinfunction "2_2") (pintype "passive"))
    )
    (net (code "6") (name "D+") (class "Default")
      (node (ref "R18") (pin "1") (pinfunction "1_1") (pintype "passive"))
      (node (ref "U$2") (pin "3") (pinfunction "3_3") (pintype "input"))
    )
    (net (code "7") (name "D-") (class "Default")
      (node (ref "R19") (pin "1") (pinfunction "1_1") (pintype "passive"))
      (node (ref "U$2") (pin "2") (pinfunction "2_2") (pintype "input"))
    )
    (net (code "8") (name "DISC") (class "Default")
      (node (ref "IC1") (pin "25") (pinfunction "PC5-ETHRXD1-ADC15_25") (pintype "bidirectional"))
      (node (ref "R26") (pin "2") (pinfunction "2_2") (pintype "passive"))
    )
    (net (code "9") (name "EINT") (class "Default")
      (node (ref "IC1") (pin "54") (pinfunction "PD2-TIM3ETR/UART5RX/SDIOCMD/DCMID11_54") (pintype "bidirectional"))
      (node (ref "P2") (pin "2") (pinfunction "2_2") (pintype "passive"))
    )
    (net (code "10") (name "EN") (class "Default")
      (node (ref "P4_PWRSW1") (pin "1") (pinfunction "1_1") (pintype "passive"))
      (node (ref "R2") (pin "2") (pinfunction "2_2") (pintype "passive"))
      (node (ref "U3") (pin "6") (pinfunction "EN_6") (pintype "input"))
      (node (ref "U3") (pin "8") (pinfunction "PS_8") (pintype "input"))
    )
    (net (code "11") (name "ESP_DTR") (class "Default")
      (node (ref "IC1") (pin "14") (pinfunction "PA0-USART2CTS/USART4TX/ETHCRS/TIM2CH1ETR/TIM5CH1/TIM8ETR-ADC0/WKUP_14") (pintype "bidirectional"))
      (node (ref "P3_ESP32_PROG") (pin "3") (pinfunction "3_3") (pintype "passive"))
      (node (ref "R30") (pin "1") (pinfunction "1_1") (pintype "passive"))
      (node (ref "T4") (pin "C") (pinfunction "C_C") (pintype "passive"))
    )
    (net (code "12") (name "ESP_EN") (class "Default")
      (node (ref "C5") (pin "2") (pinfunction "2_2") (pintype "passive"))
      (node (ref "R14") (pin "1") (pinfunction "1_1") (pintype "passive"))
      (node (ref "T3") (pin "C") (pinfunction "C_C") (pintype "passive"))
      (node (ref "U1") (pin "3") (pinfunction "EN_3") (pintype "bidirectional"))
    )
    (net (code "13") (name "ESP_RTS") (class "Default")
      (node (ref "IC1") (pin "15") (pinfunction "PA1-USART2RTS/USART4RX/ETHREFCLK/ETHRXCLK/TIM5CH2/TIM2CH2-ADC1_15") (pintype "bidirectional"))
      (node (ref "P3_ESP32_PROG") (pin "4") (pinfunction "4_4") (pintype "passive"))
      (node (ref "R31") (pin "1") (pinfunction "1_1") (pintype "passive"))
      (node (ref "T3") (pin "E") (pinfunction "E_E") (pintype "passive"))
    )
    (net (code "14") (name "ESP_RX") (class "Default")
      (node (ref "IC1") (pin "16") (pinfunction "PA2-USART2TX/TIM5CH3/TIM9CH1/TIM2CH3/ETHMDIO-ADC2_16") (pintype "bidirectional"))
      (node (ref "R11") (pin "2") (pinfunction "2_2") (pintype "passive"))
    )
    (net (code "15") (name "ESP_RXD") (class "Default")
      (node (ref "P3_ESP32_PROG") (pin "2") (pinfunction "2_2") (pintype "passive"))
      (node (ref "R11") (pin "1") (pinfunction "1_1") (pintype "passive"))
      (node (ref "U1") (pin "34") (pinfunction "RXD_34") (pintype "bidirectional"))
    )
    (net (code "16") (name "ESP_TX") (class "Default")
      (node (ref "IC1") (pin "17") (pinfunction "PA3-USART2RX/TIM5CH4/TIM9CH2/TIM2CH4/OTGD0/ETHCOL-ADC3_17") (pintype "bidirectional"))
      (node (ref "R12") (pin "2") (pinfunction "2_2") (pintype "passive"))
    )
    (net (code "17") (name "ESP_TXD") (class "Default")
      (node (ref "P3_ESP32_PROG") (pin "1") (pinfunction "1_1") (pintype "passive"))
      (node (ref "R12") (pin "1") (pinfunction "1_1") (pintype "passive"))
      (node (ref "U1") (pin "35") (pinfunction "TXD_35") (pintype "bidirectional"))
    )
    (net (code "18") (name "FB") (class "Default")
      (node (ref "R1") (pin "1") (pinfunction "1_1") (pintype "passive"))
      (node (ref "R6") (pin "2") (pinfunction "2_2") (pintype "passive"))
      (node (ref "U3") (pin "10") (pinfunction "FB_10") (pintype "passive"))
    )
    (net (code "19") (name "GND") (class "Default")
      (node (ref "C1") (pin "2") (pinfunction "2_2") (pintype "passive"))
      (node (ref "C10") (pin "2") (pinfunction "2_2") (pintype "passive"))
      (node (ref "C11") (pin "1") (pinfunction "1_1") (pintype "passive"))
      (node (ref "C12") (pin "1") (pinfunction "1_1") (pintype "passive"))
      (node (ref "C13") (pin "1") (pinfunction "1_1") (pintype "passive"))
      (node (ref "C14") (pin "1") (pinfunction "1_1") (pintype "passive"))
      (node (ref "C15") (pin "1") (pinfunction "1_1") (pintype "passive"))
      (node (ref "C16") (pin "1") (pinfunction "1_1") (pintype "passive"))
      (node (ref "C17") (pin "2") (pinfunction "2_2") (pintype "passive"))
      (node (ref "C18") (pin "2") (pinfunction "2_2") (pintype "passive"))
      (node (ref "C19") (pin "1") (pinfunction "1_1") (pintype "passive"))
      (node (ref "C20") (pin "1") (pinfunction "1_1") (pintype "passive"))
      (node (ref "C21") (pin "1") (pinfunction "1_1") (pintype "passive"))
      (node (ref "C22") (pin "1") (pinfunction "1_1") (pintype "passive"))
      (node (ref "C23") (pin "2") (pinfunction "2_2") (pintype "passive"))
      (node (ref "C24") (pin "2") (pinfunction "2_2") (pintype "passive"))
      (node (ref "C25") (pin "-") (pinfunction "-_-") (pintype "passive"))
      (node (ref "C26") (pin "-") (pinfunction "-_-") (pintype "passive"))
      (node (ref "C27") (pin "-") (pinfunction "-_-") (pintype "passive"))
      (node (ref "C28") (pin "1") (pinfunction "1_1") (pintype "passive"))
      (node (ref "C3") (pin "2") (pinfunction "2_2") (pintype "passive"))
      (node (ref "C4") (pin "2") (pinfunction "2_2") (pintype "passive"))
      (node (ref "C5") (pin "1") (pinfunction "1_1") (pintype "passive"))
      (node (ref "C6") (pin "2") (pinfunction "2_2") (pintype "passive"))
      (node (ref "C7") (pin "2") (pinfunction "2_2") (pintype "passive"))
      (node (ref "C8") (pin "1") (pinfunction "1_1") (pintype "passive"))
      (node (ref "C9") (pin "2") (pinfunction "2_2") (pintype "passive"))
      (node (ref "H5") (pin "B3,6") (pinfunction "MOUNT_B3,6") (pintype "passive"))
      (node (ref "H6") (pin "B3,6") (pinfunction "MOUNT_B3,6") (pintype "passive"))
      (node (ref "H7") (pin "B3,6") (pinfunction "MOUNT_B3,6") (pintype "passive"))
      (node (ref "H8") (pin "B3,6") (pinfunction "MOUNT_B3,6") (pintype "passive"))
      (node (ref "IC1") (pin "12") (pinfunction "VSSA_12") (pintype "power_in"))
      (node (ref "IC1") (pin "18") (pinfunction "VSS1_18") (pintype "power_in"))
      (node (ref "IC1") (pin "63") (pinfunction "VSS4_63") (pintype "bidirectional"))
      (node (ref "IC2") (pin "1") (pinfunction "ADJ_1") (pintype "input"))
      (node (ref "JP9") (pin "2") (pinfunction "2_2") (pintype "passive"))
      (node (ref "P1_GPS") (pin "4") (pinfunction "4_4") (pintype "passive"))
      (node (ref "P1_LIDAR_DATA") (pin "4") (pinfunction "4_4") (pintype "passive"))
      (node (ref "P2") (pin "5") (pinfunction "5_5") (pintype "passive"))
      (node (ref "P2_ACTOR1") (pin "6") (pinfunction "6_6") (pintype "passive"))
      (node (ref "P2_ACTOR2") (pin "6") (pinfunction "6_6") (pintype "passive"))
      (node (ref "P3_ESP32_PROG") (pin "5") (pinfunction "5_5") (pintype "passive"))
      (node (ref "P4_PWRSW1") (pin "2") (pinfunction "2_2") (pintype "passive"))
      (node (ref "P4_PWRSW2") (pin "2") (pinfunction "2_2") (pintype "passive"))
      (node (ref "Q1") (pin "2") (pinfunction "S_2") (pintype "passive"))
      (node (ref "Q4") (pin "2") (pinfunction "S_2") (pintype "passive"))
      (node (ref "Q5") (pin "2") (pinfunction "S_2") (pintype "passive"))
      (node (ref "Q6") (pin "2") (pinfunction "S_2") (pintype "passive"))
      (node (ref "Q7") (pin "2") (pinfunction "S_2") (pintype "passive"))
      (node (ref "Q8") (pin "2") (pinfunction "S_2") (pintype "passive"))
      (node (ref "R15") (pin "2") (pinfunction "2_2") (pintype "passive"))
      (node (ref "R20") (pin "1") (pinfunction "1_1") (pintype "passive"))
      (node (ref "R29") (pin "1") (pinfunction "1_1") (pintype "passive"))
      (node (ref "R39") (pin "2") (pinfunction "2_2") (pintype "passive"))
      (node (ref "R4") (pin "1") (pinfunction "1_1") (pintype "passive"))
      (node (ref "R40") (pin "2") (pinfunction "2_2") (pintype "passive"))
      (node (ref "R41") (pin "2") (pinfunction "2_2") (pintype "passive"))
      (node (ref "R42") (pin "2") (pinfunction "2_2") (pintype "passive"))
      (node (ref "R43") (pin "1") (pinfunction "1_1") (pintype "passive"))
      (node (ref "R44") (pin "1") (pinfunction "1_1") (pintype "passive"))
      (node (ref "R5") (pin "2") (pinfunction "2_2") (pintype "passive"))
      (node (ref "R6") (pin "1") (pinfunction "1_1") (pintype "passive"))
      (node (ref "SJ1") (pin "3") (pinfunction "3_3") (pintype "passive"))
      (node (ref "SJ2") (pin "3") (pinfunction "3_3") (pintype "passive"))
      (node (ref "SWD") (pin "3") (pinfunction "3_3") (pintype "passive"))
      (node (ref "T2") (pin "E") (pinfunction "E_E") (pintype "passive"))
      (node (ref "U$1") (pin "1") (pinfunction "RESV_1") (pintype "bidirectional"))
      (node (ref "U$1") (pin "18") (pinfunction "GND_18") (pintype "bidirectional"))
      (node (ref "U$1") (pin "22") (pinfunction "NCS_22") (pintype "bidirectional"))
      (node (ref "U$1") (pin "25") (pinfunction "PAD_25") (pintype "bidirectional"))
      (node (ref "U$2") (pin "5") (pinfunction "5_5") (pintype "input"))
      (node (ref "U$2") (pin "CASING1") (pinfunction "GND1_CASING1") (pintype "bidirectional"))
      (node (ref "U$2") (pin "CASING2") (pinfunction "GND2_CASING2") (pintype "bidirectional"))
      (node (ref "U$2") (pin "CASING3") (pinfunction "GND3_CASING3") (pintype "bidirectional"))
      (node (ref "U$2") (pin "CASING4") (pinfunction "GND4_CASING4") (pintype "bidirectional"))
      (node (ref "U1") (pin "1") (pinfunction "GND_1") (pintype "bidirectional"))
      (node (ref "U1") (pin "15") (pinfunction "GND_15") (pintype "bidirectional"))
      (node (ref "U1") (pin "38") (pinfunction "GND_38") (pintype "bidirectional"))
      (node (ref "U1") (pin "GND") (pinfunction "GND_GND") (pintype "bidirectional"))
      (node (ref "U2") (pin "2") (pinfunction "VSS_2") (pintype "power_in"))
      (node (ref "U3") (pin "11") (pinfunction "PAD_11") (pintype "power_in"))
      (node (ref "U3") (pin "12") (pinfunction "PAD_12") (pintype "power_in"))
      (node (ref "U3") (pin "13") (pinfunction "PAD_13") (pintype "power_in"))
      (node (ref "U3") (pin "14") (pinfunction "PAD_14") (pintype "power_in"))
      (node (ref "U3") (pin "15") (pinfunction "PAD_15") (pintype "power_in"))
      (node (ref "U3") (pin "4") (pinfunction "PGND_4") (pintype "power_in"))
      (node (ref "U3") (pin "9") (pinfunction "GND_9") (pintype "power_in"))
    )
    (net (code "20") (name "IO0") (class "Default")
      (node (ref "R13") (pin "1") (pinfunction "1_1") (pintype "passive"))
      (node (ref "T4") (pin "E") (pinfunction "E_E") (pintype "passive"))
      (node (ref "U1") (pin "25") (pinfunction "IO0_25") (pintype "bidirectional"))
    )
    (net (code "21") (name "LIDAR_PWM") (class "Default")
      (node (ref "IC1") (pin "51") (pinfunction "PC10-SPI3SCK/I2S3CK/UART4TX/SDIOD2/DCMID8/USART3TX_51") (pintype "bidirectional"))
      (node (ref "R7") (pin "2") (pinfunction "2_2") (pintype "passive"))
    )
    (net (code "22") (name "LIDAR_RX") (class "Default")
      (node (ref "IC1") (pin "53") (pinfunction "PC12-UART5TX/SDIOCK/DCMID9/SPI3MOSI/I2S3SD/USART3CK_53") (pintype "bidirectional"))
      (node (ref "R10") (pin "2") (pinfunction "2_2") (pintype "passive"))
    )
    (net (code "23") (name "LIDAR_TX") (class "Default")
      (node (ref "IC1") (pin "52") (pinfunction "PC11-UART4RX/SPI3MISO/SDIOD3/DCMID4/USART3RX/I2S3EXTSD_52") (pintype "bidirectional"))
      (node (ref "R8") (pin "2") (pinfunction "2_2") (pintype "passive"))
    )
    (net (code "24") (name "M1") (class "Default")
      (node (ref "IC1") (pin "30") (pinfunction "PB11-I2C2SDA/USART3RX/OTGD4/ETHTXEN/TIM2CH4_30") (pintype "bidirectional"))
      (node (ref "R38") (pin "1") (pinfunction "1_1") (pintype "passive"))
    )
    (net (code "25") (name "M2") (class "Default")
      (node (ref "IC1") (pin "33") (pinfunction "PB12-SPI2NSS/I2S2WS/I2C2SMBA/USART3CK/TIM1BKIN/CAN2RX/OTGD5/ETHTXD0/OTGID_33") (pintype "bidirectional"))
      (node (ref "R37") (pin "1") (pinfunction "1_1") (pintype "passive"))
    )
    (net (code "26") (name "M3") (class "Default")
      (node (ref "IC1") (pin "34") (pinfunction "PB13-SPI2SCK/I2S2CK/USART3CTS/TIM1CH1N/CAN2TX/OTGD6/ETHTXD1-OTGVBUS_34") (pintype "bidirectional"))
      (node (ref "R36") (pin "1") (pinfunction "1_1") (pintype "passive"))
    )
    (net (code "27") (name "M4") (class "Default")
      (node (ref "IC1") (pin "35") (pinfunction "PB14-SPI2MISO/TIM1CH2N/TIM12CH1/OTGDM/USART3RTS/TIM8CH3N/12S2EXTSD_35") (pintype "bidirectional"))
      (node (ref "R35") (pin "1") (pinfunction "1_1") (pintype "passive"))
    )
    (net (code "28") (name "M5") (class "Default")
      (node (ref "IC1") (pin "36") (pinfunction "PB15-SPI2MOSI/I2S2SD/TIM1CH3N/TIM8CH3N/TIM12CH2/OTGDP-RTCREFIN_36") (pintype "bidirectional"))
      (node (ref "R34") (pin "1") (pinfunction "1_1") (pintype "passive"))
    )
    (net (code "29") (name "MPU_INT") (class "Default")
      (node (ref "IC1") (pin "57") (pinfunction "PB5-I2C1SMBA/CAN2RX/OTGD7/ETHPPSOUT/TIM3CH2/SPI1MOSI/SPI3MOSI/DCMID10/I2S3SD_57") (pintype "bidirectional"))
      (node (ref "U$1") (pin "12") (pinfunction "INT_12") (pintype "bidirectional"))
    )
    (net (code "30") (name "N$10") (class "Default")
      (node (ref "IC1") (pin "8") (pinfunction "PC0-OTGSTP-ADC10_8") (pintype "bidirectional"))
      (node (ref "P2_ACTOR1") (pin "2") (pinfunction "2_2") (pintype "passive"))
    )
    (net (code "31") (name "N$36") (class "Default")
      (node (ref "IC1") (pin "9") (pinfunction "PC1-ETHMDC-ADC11_9") (pintype "bidirectional"))
      (node (ref "P2_ACTOR1") (pin "3") (pinfunction "3_3") (pintype "passive"))
    )
    (net (code "32") (name "N$37") (class "Default")
      (node (ref "IC1") (pin "10") (pinfunction "PC2-SPI2MISO/OTGDIR/ETHTXD2/I2S2EXTSD-ADC12_10") (pintype "bidirectional"))
      (node (ref "P2_ACTOR1") (pin "4") (pinfunction "4_4") (pintype "passive"))
    )
    (net (code "33") (name "N$38") (class "Default")
      (node (ref "IC1") (pin "11") (pinfunction "PC3-SPI2MOSI/I2S2SD/OTGNXT/ETHTXCLK-ADC13_11") (pintype "bidirectional"))
      (node (ref "P2_ACTOR1") (pin "5") (pinfunction "5_5") (pintype "passive"))
    )
    (net (code "34") (name "N$39") (class "Default")
      (node (ref "D5") (pin "A") (pinfunction "A_A") (pintype "passive"))
      (node (ref "P2_ACTOR2") (pin "5") (pinfunction "5_5") (pintype "passive"))
      (node (ref "U1") (pin "10") (pinfunction "IO25_10") (pintype "bidirectional"))
    )
    (net (code "35") (name "N$40") (class "Default")
      (node (ref "D3") (pin "A") (pinfunction "A_A") (pintype "passive"))
      (node (ref "P2_ACTOR2") (pin "4") (pinfunction "4_4") (pintype "passive"))
      (node (ref "U1") (pin "11") (pinfunction "IO26_11") (pintype "bidirectional"))
    )
    (net (code "36") (name "N$41") (class "Default")
      (node (ref "D2") (pin "A") (pinfunction "A_A") (pintype "passive"))
      (node (ref "P2_ACTOR2") (pin "3") (pinfunction "3_3") (pintype "passive"))
      (node (ref "U1") (pin "12") (pinfunction "IO27_12") (pintype "bidirectional"))
    )
    (net (code "37") (name "N$42") (class "Default")
      (node (ref "D1") (pin "A") (pinfunction "A_A") (pintype "passive"))
      (node (ref "P2_ACTOR2") (pin "2") (pinfunction "2_2") (pintype "passive"))
      (node (ref "U1") (pin "13") (pinfunction "IO14_13") (pintype "bidirectional"))
    )
    (net (code "38") (name "NRST") (class "Default")
      (node (ref "C14") (pin "2") (pinfunction "2_2") (pintype "passive"))
      (node (ref "IC1") (pin "7") (pinfunction "NRST_7") (pintype "bidirectional"))
      (node (ref "R16") (pin "1") (pinfunction "1_1") (pintype "passive"))
      (node (ref "SWD") (pin "5") (pinfunction "5_5") (pintype "passive"))
    )
    (net (code "39") (name "Net-(D1-PadC)") (class "Default")
      (node (ref "D1") (pin "C") (pinfunction "C_C") (pintype "passive"))
      (node (ref "R39") (pin "1") (pinfunction "1_1") (pintype "passive"))
    )
    (net (code "40") (name "Net-(D2-PadC)") (class "Default")
      (node (ref "D2") (pin "C") (pinfunction "C_C") (pintype "passive"))
      (node (ref "R40") (pin "1") (pinfunction "1_1") (pintype "passive"))
    )
    (net (code "41") (name "Net-(D3-PadC)") (class "Default")
      (node (ref "D3") (pin "C") (pinfunction "C_C") (pintype "passive"))
      (node (ref "R41") (pin "1") (pinfunction "1_1") (pintype "passive"))
    )
    (net (code "42") (name "Net-(D4-PadC)") (class "Default")
      (node (ref "D4") (pin "C") (pinfunction "C_C") (pintype "passive"))
      (node (ref "R9") (pin "2") (pinfunction "2_2") (pintype "passive"))
    )
    (net (code "43") (name "Net-(D5-PadC)") (class "Default")
      (node (ref "D5") (pin "C") (pinfunction "C_C") (pintype "passive"))
      (node (ref "R42") (pin "1") (pinfunction "1_1") (pintype "passive"))
    )
    (net (code "44") (name "Net-(D6-PadA)") (class "Default")
      (node (ref "D6") (pin "A") (pinfunction "A_A") (pintype "passive"))
      (node (ref "R43") (pin "2") (pinfunction "2_2") (pintype "passive"))
    )
    (net (code "45") (name "Net-(D7-PadA)") (class "Default")
      (node (ref "D7") (pin "A") (pinfunction "A_A") (pintype "passive"))
      (node (ref "R44") (pin "2") (pinfunction "2_2") (pintype "passive"))
    )
    (net (code "46") (name "Net-(IC1-PC6-I2S2MCK{slash}TIM8CH1{slash}SDIOD6{slash}USART6TX{slash}DCMID0{slash}TIM3CH1)") (class "Default")
      (node (ref "D6") (pin "C") (pinfunction "C_C") (pintype "passive"))
      (node (ref "IC1") (pin "37") (pinfunction "PC6-I2S2MCK/TIM8CH1/SDIOD6/USART6TX/DCMID0/TIM3CH1_37") (pintype "bidirectional"))
    )
    (net (code "47") (name "Net-(IC1-PC7-I2S3MCK{slash}TIM8CH2{slash}SDIOD7{slash}USART6RX{slash}DCMID1{slash}TIM3CH2)") (class "Default")
      (node (ref "D7") (pin "C") (pinfunction "C_C") (pintype "passive"))
      (node (ref "IC1") (pin "38") (pinfunction "PC7-I2S3MCK/TIM8CH2/SDIOD7/USART6RX/DCMID1/TIM3CH2_38") (pintype "bidirectional"))
    )
    (net (code "48") (name "Net-(IC1-PC14{slash}OSC32IN--OSC32IN)") (class "Default")
      (node (ref "C20") (pin "2") (pinfunction "2_2") (pintype "passive"))
      (node (ref "IC1") (pin "3") (pinfunction "PC14/OSC32IN--OSC32IN_3") (pintype "bidirectional"))
      (node (ref "Q3") (pin "2") (pinfunction "2_2") (pintype "passive"))
    )
    (net (code "49") (name "Net-(IC1-PC15{slash}OSC32OUT--OSC32OUT)") (class "Default")
      (node (ref "C19") (pin "2") (pinfunction "2_2") (pintype "passive"))
      (node (ref "IC1") (pin "4") (pinfunction "PC15/OSC32OUT--OSC32OUT_4") (pintype "bidirectional"))
      (node (ref "Q3") (pin "1") (pinfunction "1_1") (pintype "passive"))
    )
    (net (code "50") (name "Net-(IC1-PH0{slash}OSCIN--OSCIN)") (class "Default")
      (node (ref "C18") (pin "1") (pinfunction "1_1") (pintype "passive"))
      (node (ref "IC1") (pin "5") (pinfunction "PH0/OSCIN--OSCIN_5") (pintype "input"))
      (node (ref "Q2") (pin "2") (pinfunction "2_2") (pintype "passive"))
      (node (ref "R17") (pin "2") (pinfunction "2_2") (pintype "passive"))
    )
    (net (code "51") (name "Net-(IC1-PH1{slash}OSCOUT--OSCOUT)") (class "Default")
      (node (ref "C17") (pin "1") (pinfunction "1_1") (pintype "passive"))
      (node (ref "IC1") (pin "6") (pinfunction "PH1/OSCOUT--OSCOUT_6") (pintype "output"))
      (node (ref "Q2") (pin "1") (pinfunction "1_1") (pintype "passive"))
      (node (ref "R17") (pin "1") (pinfunction "1_1") (pintype "passive"))
    )
    (net (code "52") (name "Net-(IC1-VCAP1)") (class "Default")
      (node (ref "C6") (pin "1") (pinfunction "1_1") (pintype "passive"))
      (node (ref "IC1") (pin "31") (pinfunction "VCAP1_31") (pintype "power_in"))
    )
    (net (code "53") (name "Net-(IC1-VCAP2)") (class "Default")
      (node (ref "C7") (pin "1") (pinfunction "1_1") (pintype "passive"))
      (node (ref "IC1") (pin "47") (pinfunction "VCAP2_47") (pintype "power_in"))
    )
    (net (code "54") (name "Net-(L1-1)") (class "Default")
      (node (ref "L1") (pin "P$1") (pinfunction "1_P$1") (pintype "passive"))
      (node (ref "U3") (pin "3") (pinfunction "L_3") (pintype "passive"))
    )
    (net (code "55") (name "Net-(P1_LIDAR_DATA-Pad2)") (class "Default")
      (node (ref "P1_LIDAR_DATA") (pin "2") (pinfunction "2_2") (pintype "passive"))
      (node (ref "R8") (pin "1") (pinfunction "1_1") (pintype "passive"))
    )
    (net (code "56") (name "Net-(P1_LIDAR_DATA-Pad3)") (class "Default")
      (node (ref "P1_LIDAR_DATA") (pin "3") (pinfunction "3_3") (pintype "passive"))
      (node (ref "R10") (pin "1") (pinfunction "1_1") (pintype "passive"))
    )
    (net (code "57") (name "Net-(P2_ACTOR-Pad6)") (class "Default")
      (node (ref "P2_ACTOR") (pin "6") (pinfunction "6_6") (pintype "passive"))
      (node (ref "SJ3") (pin "2") (pinfunction "2_2") (pintype "passive"))
    )
    (net (code "58") (name "Net-(Q1-D)") (class "Default")
      (node (ref "P4_LIDAR_MOTOR") (pin "2") (pinfunction "2_2") (pintype "passive"))
      (node (ref "Q1") (pin "3") (pinfunction "D_3") (pintype "passive"))
    )
    (net (code "59") (name "Net-(Q1-G)") (class "Default")
      (node (ref "Q1") (pin "1") (pinfunction "G_1") (pintype "passive"))
      (node (ref "R7") (pin "1") (pinfunction "1_1") (pintype "passive"))
    )
    (net (code "60") (name "Net-(Q4-D)") (class "Default")
      (node (ref "P2_ACTOR") (pin "5") (pinfunction "5_5") (pintype "passive"))
      (node (ref "Q4") (pin "3") (pinfunction "D_3") (pintype "passive"))
    )
    (net (code "61") (name "Net-(Q4-G)") (class "Default")
      (node (ref "Q4") (pin "1") (pinfunction "G_1") (pintype "passive"))
      (node (ref "R34") (pin "2") (pinfunction "2_2") (pintype "passive"))
    )
    (net (code "62") (name "Net-(Q5-D)") (class "Default")
      (node (ref "P2_ACTOR") (pin "4") (pinfunction "4_4") (pintype "passive"))
      (node (ref "Q5") (pin "3") (pinfunction "D_3") (pintype "passive"))
    )
    (net (code "63") (name "Net-(Q5-G)") (class "Default")
      (node (ref "Q5") (pin "1") (pinfunction "G_1") (pintype "passive"))
      (node (ref "R35") (pin "2") (pinfunction "2_2") (pintype "passive"))
    )
    (net (code "64") (name "Net-(Q6-D)") (class "Default")
      (node (ref "P2_ACTOR") (pin "3") (pinfunction "3_3") (pintype "passive"))
      (node (ref "Q6") (pin "3") (pinfunction "D_3") (pintype "passive"))
    )
    (net (code "65") (name "Net-(Q6-G)") (class "Default")
      (node (ref "Q6") (pin "1") (pinfunction "G_1") (pintype "passive"))
      (node (ref "R36") (pin "2") (pinfunction "2_2") (pintype "passive"))
    )
    (net (code "66") (name "Net-(Q7-D)") (class "Default")
      (node (ref "P2_ACTOR") (pin "2") (pinfunction "2_2") (pintype "passive"))
      (node (ref "Q7") (pin "3") (pinfunction "D_3") (pintype "passive"))
    )
    (net (code "67") (name "Net-(Q7-G)") (class "Default")
      (node (ref "Q7") (pin "1") (pinfunction "G_1") (pintype "passive"))
      (node (ref "R37") (pin "2") (pinfunction "2_2") (pintype "passive"))
    )
    (net (code "68") (name "Net-(Q8-D)") (class "Default")
      (node (ref "P2_ACTOR") (pin "1") (pinfunction "1_1") (pintype "passive"))
      (node (ref "Q8") (pin "3") (pinfunction "D_3") (pintype "passive"))
    )
    (net (code "69") (name "Net-(Q8-G)") (class "Default")
      (node (ref "Q8") (pin "1") (pinfunction "G_1") (pintype "passive"))
      (node (ref "R38") (pin "2") (pinfunction "2_2") (pintype "passive"))
    )
    (net (code "70") (name "Net-(R20-Pad2)") (class "Default")
      (node (ref "R20") (pin "2") (pinfunction "2_2") (pintype "passive"))
      (node (ref "R23") (pin "1") (pinfunction "1_1") (pintype "passive"))
      (node (ref "T1") (pin "B") (pinfunction "B_B") (pintype "passive"))
      (node (ref "T2") (pin "C") (pinfunction "C_C") (pintype "passive"))
    )
    (net (code "71") (name "Net-(R21-Pad1)") (class "Default")
      (node (ref "R21") (pin "1") (pinfunction "1_1") (pintype "passive"))
      (node (ref "SJ1") (pin "2") (pinfunction "2_2") (pintype "passive"))
    )
    (net (code "72") (name "Net-(R22-Pad1)") (class "Default")
      (node (ref "R22") (pin "1") (pinfunction "1_1") (pintype "passive"))
      (node (ref "SJ2") (pin "2") (pinfunction "2_2") (pintype "passive"))
    )
    (net (code "73") (name "Net-(R23-Pad2)") (class "Default")
      (node (ref "R23") (pin "2") (pinfunction "2_2") (pintype "passive"))
      (node (ref "R24") (pin "1") (pinfunction "1_1") (pintype "passive"))
    )
    (net (code "74") (name "Net-(R25-Pad2)") (class "Default")
      (node (ref "R25") (pin "2") (pinfunction "2_2") (pintype "passive"))
      (node (ref "T1") (pin "E") (pinfunction "E_E") (pintype "passive"))
    )
    (net (code "75") (name "Net-(R26-Pad1)") (class "Default")
      (node (ref "R26") (pin "1") (pinfunction "1_1") (pintype "passive"))
      (node (ref "R27") (pin "2") (pinfunction "2_2") (pintype "passive"))
      (node (ref "T2") (pin "B") (pinfunction "B_B") (pintype "passive"))
    )
    (net (code "76") (name "Net-(R30-Pad2)") (class "Default")
      (node (ref "R30") (pin "2") (pinfunction "2_2") (pintype "passive"))
      (node (ref "T3") (pin "B") (pinfunction "B_B") (pintype "passive"))
    )
    (net (code "77") (name "Net-(R31-Pad2)") (class "Default")
      (node (ref "R31") (pin "2") (pinfunction "2_2") (pintype "passive"))
      (node (ref "T4") (pin "B") (pinfunction "B_B") (pintype "passive"))
    )
    (net (code "78") (name "Net-(U$1-REGOUT)") (class "Default")
      (node (ref "C23") (pin "1") (pinfunction "1_1") (pintype "passive"))
      (node (ref "U$1") (pin "10") (pinfunction "REGOUT_10") (pintype "bidirectional"))
    )
    (net (code "79") (name "Net-(U$1-RESV2)") (class "Default")
      (node (ref "C28") (pin "2") (pinfunction "2_2") (pintype "passive"))
      (node (ref "U$1") (pin "20") (pinfunction "RESV2_20") (pintype "bidirectional"))
    )
    (net (code "80") (name "Net-(U1-IO2)") (class "Default")
      (node (ref "R15") (pin "1") (pinfunction "1_1") (pintype "passive"))
      (node (ref "U1") (pin "24") (pinfunction "IO2_24") (pintype "bidirectional"))
    )
    (net (code "81") (name "Net-(U2-PROG)") (class "Default")
      (node (ref "R5") (pin "1") (pinfunction "1_1") (pintype "passive"))
      (node (ref "U2") (pin "5") (pinfunction "PROG_5") (pintype "input"))
    )
    (net (code "82") (name "Net-(U2-STAT)") (class "Default")
      (node (ref "R9") (pin "1") (pinfunction "1_1") (pintype "passive"))
      (node (ref "U2") (pin "1") (pinfunction "STAT_1") (pintype "output"))
    )
    (net (code "83") (name "Net-(U3-UVLO)") (class "Default")
      (node (ref "C2") (pin "2") (pinfunction "2_2") (pintype "passive"))
      (node (ref "R3") (pin "1") (pinfunction "1_1") (pintype "passive"))
      (node (ref "R4") (pin "2") (pinfunction "2_2") (pintype "passive"))
      (node (ref "U3") (pin "7") (pinfunction "UVLO_7") (pintype "passive"))
    )
    (net (code "84") (name "Net-(U3-VAUX)") (class "Default")
      (node (ref "C4") (pin "1") (pinfunction "1_1") (pintype "passive"))
      (node (ref "U3") (pin "1") (pinfunction "VAUX_1") (pintype "passive"))
    )
    (net (code "85") (name "SCL") (class "Default")
      (node (ref "IC1") (pin "58") (pinfunction "PB6-I2C1SCL/TIM4CH1/CAN2TX/DCMID5/USART1TX_58") (pintype "bidirectional"))
      (node (ref "P2") (pin "3") (pinfunction "3_3") (pintype "passive"))
      (node (ref "R32") (pin "2") (pinfunction "2_2") (pintype "passive"))
      (node (ref "U$1") (pin "23") (pinfunction "SCL/SCLK_23") (pintype "bidirectional"))
    )
    (net (code "86") (name "SDA") (class "Default")
      (node (ref "IC1") (pin "59") (pinfunction "PB7-I2C1SDA/FSMCNL/DCMIVSYNC/USART1RX/TIM4CH2_59") (pintype "bidirectional"))
      (node (ref "P2") (pin "4") (pinfunction "4_4") (pintype "passive"))
      (node (ref "R33") (pin "2") (pinfunction "2_2") (pintype "passive"))
      (node (ref "U$1") (pin "24") (pinfunction "SDA/SDI_24") (pintype "bidirectional"))
    )
    (net (code "87") (name "SWCLK") (class "Default")
      (node (ref "IC1") (pin "49") (pinfunction "PA14/JTCK/SWCLK_49") (pintype "bidirectional"))
      (node (ref "SWD") (pin "2") (pinfunction "2_2") (pintype "passive"))
    )
    (net (code "88") (name "SWDIO") (class "Default")
      (node (ref "IC1") (pin "46") (pinfunction "PA13/JTMS/SWDIO_46") (pintype "bidirectional"))
      (node (ref "SWD") (pin "4") (pinfunction "4_4") (pintype "passive"))
    )
    (net (code "89") (name "TRACESWO") (class "Default")
      (node (ref "IC1") (pin "55") (pinfunction "PB3/JTDO/TRACESWO-SPI3SCK/I2S3CK/TIM2CH2/SPI1SCK_55") (pintype "bidirectional"))
      (node (ref "SWD") (pin "6") (pinfunction "6_6") (pintype "passive"))
    )
    (net (code "90") (name "UART1_TX") (class "Default")
      (node (ref "IC1") (pin "42") (pinfunction "PA9-USART1TX/TIM1CH2/I2C3SMBA/DCMID0-OTGFSVBUS_42") (pintype "bidirectional"))
      (node (ref "P1_GPS") (pin "2") (pinfunction "2_2") (pintype "passive"))
    )
    (net (code "91") (name "UART2_RX") (class "Default")
      (node (ref "IC1") (pin "43") (pinfunction "PA10-USART1RX/TIM1CH3/OTGFSID/DCMID1_43") (pintype "bidirectional"))
      (node (ref "P1_GPS") (pin "3") (pinfunction "3_3") (pintype "passive"))
    )
    (net (code "92") (name "USBP_E") (class "Default")
      (node (ref "IC1") (pin "24") (pinfunction "PC4-ETHRXD0-ADC14_24") (pintype "bidirectional"))
      (node (ref "R28") (pin "1") (pinfunction "1_1") (pintype "passive"))
      (node (ref "R29") (pin "2") (pinfunction "2_2") (pintype "passive"))
    )
    (net (code "93") (name "USB_D+") (class "Default")
      (node (ref "IC1") (pin "45") (pinfunction "PA12-USART1RTS/CAN1TX/TIM1ETR/OTGFSDP_45") (pintype "bidirectional"))
      (node (ref "R18") (pin "2") (pinfunction "2_2") (pintype "passive"))
      (node (ref "R25") (pin "1") (pinfunction "1_1") (pintype "passive"))
    )
    (net (code "94") (name "USB_D-") (class "Default")
      (node (ref "IC1") (pin "44") (pinfunction "PA11-USART1CTS/CAN1RX/TIM1CH4/OTGFSDM_44") (pintype "bidirectional"))
      (node (ref "R19") (pin "2") (pinfunction "2_2") (pintype "passive"))
    )
    (net (code "95") (name "VBATT") (class "Default")
      (node (ref "C1") (pin "1") (pinfunction "1_1") (pintype "passive"))
      (node (ref "C10") (pin "1") (pinfunction "1_1") (pintype "passive"))
      (node (ref "C2") (pin "1") (pinfunction "1_1") (pintype "passive"))
      (node (ref "L1") (pin "P$2") (pinfunction "2_P$2") (pintype "passive"))
      (node (ref "P4_PWRSW2") (pin "1") (pinfunction "1_1") (pintype "passive"))
      (node (ref "R2") (pin "1") (pinfunction "1_1") (pintype "passive"))
      (node (ref "R3") (pin "2") (pinfunction "2_2") (pintype "passive"))
      (node (ref "U2") (pin "3") (pinfunction "VBAT_3") (pintype "power_in"))
      (node (ref "U3") (pin "5") (pinfunction "VIN_5") (pintype "power_in"))
    )
    (net (code "96") (name "VBUS") (class "Default")
      (node (ref "F1") (pin "2") (pinfunction "2_2") (pintype "passive"))
      (node (ref "U$2") (pin "1") (pinfunction "1_1") (pintype "input"))
    )
    (net (code "97") (name "unconnected-(IC1-PA4-SPI1NSS{slash}SPI3NSS{slash}USART2CK{slash}DCMIHSYNC{slash}OTGSOF{slash}I2S3WS-ADC4{slash}DAC1-Pad20)") (class "Default")
      (node (ref "IC1") (pin "20") (pinfunction "PA4-SPI1NSS/SPI3NSS/USART2CK/DCMIHSYNC/OTGSOF/I2S3WS-ADC4/DAC1_20") (pintype "bidirectional"))
    )
    (net (code "98") (name "unconnected-(IC1-PA5-SPI1SCK{slash}OTGCK{slash}TIM2CH1ETR{slash}TIM8CH1N-ADC5{slash}DAC2-Pad21)") (class "Default")
      (node (ref "IC1") (pin "21") (pinfunction "PA5-SPI1SCK/OTGCK/TIM2CH1ETR/TIM8CH1N-ADC5/DAC2_21") (pintype "bidirectional"))
    )
    (net (code "99") (name "unconnected-(IC1-PA6-SPI1MISO{slash}TIM8BKIN{slash}TIM13CH1{slash}DCMIPIXCLK{slash}TIM3CH1{slash}TIM1BKIN-ADC6-Pad22)") (class "Default")
      (node (ref "IC1") (pin "22") (pinfunction "PA6-SPI1MISO/TIM8BKIN/TIM13CH1/DCMIPIXCLK/TIM3CH1/TIM1BKIN-ADC6_22") (pintype "bidirectional"))
    )
    (net (code "100") (name "unconnected-(IC1-PA7-SPI1MOSI{slash}TIM8CH1N{slash}TIM14CH1{slash}TIM3CH2{slash}ETHRXDV{slash}TIM1CH1N{slash}ETHCRSDV-ADC7-Pad23)") (class "Default")
      (node (ref "IC1") (pin "23") (pinfunction "PA7-SPI1MOSI/TIM8CH1N/TIM14CH1/TIM3CH2/ETHRXDV/TIM1CH1N/ETHCRSDV-ADC7_23") (pintype "bidirectional"))
    )
    (net (code "101") (name "unconnected-(IC1-PA8-MCO1{slash}USART1CK{slash}TIM1CH1{slash}I2C3SCL{slash}OTGSOF-Pad41)") (class "Default")
      (node (ref "IC1") (pin "41") (pinfunction "PA8-MCO1/USART1CK/TIM1CH1/I2C3SCL/OTGSOF_41") (pintype "bidirectional"))
    )
    (net (code "102") (name "unconnected-(IC1-PA15{slash}JTDI-SPI3NSS{slash}I2S3WS{slash}TIM2CH1ETR{slash}SPI1NSS-Pad50)") (class "Default")
      (node (ref "IC1") (pin "50") (pinfunction "PA15/JTDI-SPI3NSS/I2S3WS/TIM2CH1ETR/SPI1NSS_50") (pintype "bidirectional"))
    )
    (net (code "103") (name "unconnected-(IC1-PB0-TIM3CH3{slash}TIM8CH2N{slash}OTGD1{slash}ETHRXD2{slash}TIM2CH2N-ADC8-Pad26)") (class "Default")
      (node (ref "IC1") (pin "26") (pinfunction "PB0-TIM3CH3/TIM8CH2N/OTGD1/ETHRXD2/TIM2CH2N-ADC8_26") (pintype "bidirectional"))
    )
    (net (code "104") (name "unconnected-(IC1-PB2-TIM3CH4{slash}TIM8CH3N{slash}OTGD2{slash}ETHRXD3{slash}TIM1CH3N-ADC9-Pad27)") (class "Default")
      (node (ref "IC1") (pin "27") (pinfunction "PB2-TIM3CH4/TIM8CH3N/OTGD2/ETHRXD3/TIM1CH3N-ADC9_27") (pintype "bidirectional"))
    )
    (net (code "105") (name "unconnected-(IC1-PB4{slash}JNTRST-SPI3MISO{slash}TIM3CH1{slash}SPI1MISO{slash}I2S3EXTSD-Pad56)") (class "Default")
      (node (ref "IC1") (pin "56") (pinfunction "PB4/JNTRST-SPI3MISO/TIM3CH1/SPI1MISO/I2S3EXTSD_56") (pintype "bidirectional"))
    )
    (net (code "106") (name "unconnected-(IC1-PB8-TIM4CH3{slash}SDIOD4{slash}TIM10CH1{slash}DCMID6{slash}ETHTXD3{slash}I2C1SCL{slash}CAN1RX-Pad61)") (class "Default")
      (node (ref "IC1") (pin "61") (pinfunction "PB8-TIM4CH3/SDIOD4/TIM10CH1/DCMID6/ETHTXD3/I2C1SCL/CAN1RX_61") (pintype "bidirectional"))
    )
    (net (code "107") (name "unconnected-(IC1-PB9-SPI2NSS{slash}I2S2WS{slash}TIM4CH4{slash}TIM11CH1{slash}SDIOD5{slash}DCMID7{slash}I2C1SDA{slash}CAN1TX-Pad62)") (class "Default")
      (node (ref "IC1") (pin "62") (pinfunction "PB9-SPI2NSS/I2S2WS/TIM4CH4/TIM11CH1/SDIOD5/DCMID7/I2C1SDA/CAN1TX_62") (pintype "bidirectional"))
    )
    (net (code "108") (name "unconnected-(IC1-PB10-SPI2SCK{slash}I2S2CK{slash}I2C2SCL{slash}USART3TX{slash}OTGD3{slash}ETHRXER{slash}TIM2CH3-Pad29)") (class "Default")
      (node (ref "IC1") (pin "29") (pinfunction "PB10-SPI2SCK/I2S2CK/I2C2SCL/USART3TX/OTGD3/ETHRXER/TIM2CH3_29") (pintype "bidirectional"))
    )
    (net (code "109") (name "unconnected-(IC1-PC8-TIM8CH3{slash}SDIOD0{slash}TIM3CH3{slash}USART6CK{slash}DCMID2-Pad39)") (class "Default")
      (node (ref "IC1") (pin "39") (pinfunction "PC8-TIM8CH3/SDIOD0/TIM3CH3/USART6CK/DCMID2_39") (pintype "bidirectional"))
    )
    (net (code "110") (name "unconnected-(IC1-PC9-I2SCKIN{slash}MCO2{slash}TIM8CH4{slash}SDIOD1{slash}I2C3SDA{slash}DCMID3{slash}TIM3CH-Pad40)") (class "Default")
      (node (ref "IC1") (pin "40") (pinfunction "PC9-I2SCKIN/MCO2/TIM8CH4/SDIOD1/I2C3SDA/DCMID3/TIM3CH_40") (pintype "bidirectional"))
    )
    (net (code "111") (name "unconnected-(IC1-PC13--RTCO{slash}RTCTAMP1{slash}RTCTS-Pad2)") (class "Default")
      (node (ref "IC1") (pin "2") (pinfunction "PC13--RTCO/RTCTAMP1/RTCTS_2") (pintype "bidirectional"))
    )
    (net (code "112") (name "unconnected-(U$1-ADO{slash}SDO-Pad9)") (class "Default")
      (node (ref "U$1") (pin "9") (pinfunction "ADO/SDO_9") (pintype "bidirectional"))
    )
    (net (code "113") (name "unconnected-(U$1-AUX_CL-Pad7)") (class "Default")
      (node (ref "U$1") (pin "7") (pinfunction "AUX_CL_7") (pintype "bidirectional"))
    )
    (net (code "114") (name "unconnected-(U$1-AUX_DA-Pad21)") (class "Default")
      (node (ref "U$1") (pin "21") (pinfunction "AUX_DA_21") (pintype "bidirectional"))
    )
    (net (code "115") (name "unconnected-(U$1-FSYNC-Pad11)") (class "Default")
      (node (ref "U$1") (pin "11") (pinfunction "FSYNC_11") (pintype "bidirectional"))
    )
    (net (code "116") (name "unconnected-(U$1-NC1-Pad2)") (class "Default")
      (node (ref "U$1") (pin "2") (pinfunction "NC1_2") (pintype "bidirectional"))
    )
    (net (code "117") (name "unconnected-(U$1-NC2-Pad3)") (class "Default")
      (node (ref "U$1") (pin "3") (pinfunction "NC2_3") (pintype "bidirectional"))
    )
    (net (code "118") (name "unconnected-(U$1-NC3-Pad4)") (class "Default")
      (node (ref "U$1") (pin "4") (pinfunction "NC3_4") (pintype "bidirectional"))
    )
    (net (code "119") (name "unconnected-(U$1-NC4-Pad5)") (class "Default")
      (node (ref "U$1") (pin "5") (pinfunction "NC4_5") (pintype "bidirectional"))
    )
    (net (code "120") (name "unconnected-(U$1-NC5-Pad6)") (class "Default")
      (node (ref "U$1") (pin "6") (pinfunction "NC5_6") (pintype "bidirectional"))
    )
    (net (code "121") (name "unconnected-(U$1-NC6-Pad14)") (class "Default")
      (node (ref "U$1") (pin "14") (pinfunction "NC6_14") (pintype "bidirectional"))
    )
    (net (code "122") (name "unconnected-(U$1-NC7-Pad15)") (class "Default")
      (node (ref "U$1") (pin "15") (pinfunction "NC7_15") (pintype "bidirectional"))
    )
    (net (code "123") (name "unconnected-(U$1-NC8-Pad16)") (class "Default")
      (node (ref "U$1") (pin "16") (pinfunction "NC8_16") (pintype "bidirectional"))
    )
    (net (code "124") (name "unconnected-(U$1-NC9-Pad17)") (class "Default")
      (node (ref "U$1") (pin "17") (pinfunction "NC9_17") (pintype "bidirectional"))
    )
    (net (code "125") (name "unconnected-(U$1-RESV1-Pad19)") (class "Default")
      (node (ref "U$1") (pin "19") (pinfunction "RESV1_19") (pintype "bidirectional"))
    )
    (net (code "126") (name "unconnected-(U$2-Pad4)") (class "Default")
      (node (ref "U$2") (pin "4") (pinfunction "4_4") (pintype "input"))
    )
    (net (code "127") (name "unconnected-(U1-IO4-Pad26)") (class "Default")
      (node (ref "U1") (pin "26") (pinfunction "IO4_26") (pintype "bidirectional"))
    )
    (net (code "128") (name "unconnected-(U1-IO5-Pad29)") (class "Default")
      (node (ref "U1") (pin "29") (pinfunction "IO5_29") (pintype "bidirectional"))
    )
    (net (code "129") (name "unconnected-(U1-IO12-Pad14)") (class "Default")
      (node (ref "U1") (pin "14") (pinfunction "IO12_14") (pintype "bidirectional"))
    )
    (net (code "130") (name "unconnected-(U1-IO13-Pad16)") (class "Default")
      (node (ref "U1") (pin "16") (pinfunction "IO13_16") (pintype "bidirectional"))
    )
    (net (code "131") (name "unconnected-(U1-IO15-Pad23)") (class "Default")
      (node (ref "U1") (pin "23") (pinfunction "IO15_23") (pintype "bidirectional"))
    )
    (net (code "132") (name "unconnected-(U1-IO16-Pad27)") (class "Default")
      (node (ref "U1") (pin "27") (pinfunction "IO16_27") (pintype "bidirectional"))
    )
    (net (code "133") (name "unconnected-(U1-IO17-Pad28)") (class "Default")
      (node (ref "U1") (pin "28") (pinfunction "IO17_28") (pintype "bidirectional"))
    )
    (net (code "134") (name "unconnected-(U1-IO18-Pad30)") (class "Default")
      (node (ref "U1") (pin "30") (pinfunction "IO18_30") (pintype "bidirectional"))
    )
    (net (code "135") (name "unconnected-(U1-IO19-Pad31)") (class "Default")
      (node (ref "U1") (pin "31") (pinfunction "IO19_31") (pintype "bidirectional"))
    )
    (net (code "136") (name "unconnected-(U1-IO21-Pad33)") (class "Default")
      (node (ref "U1") (pin "33") (pinfunction "IO21_33") (pintype "bidirectional"))
    )
    (net (code "137") (name "unconnected-(U1-IO22-Pad36)") (class "Default")
      (node (ref "U1") (pin "36") (pinfunction "IO22_36") (pintype "bidirectional"))
    )
    (net (code "138") (name "unconnected-(U1-IO23-Pad37)") (class "Default")
      (node (ref "U1") (pin "37") (pinfunction "IO23_37") (pintype "bidirectional"))
    )
    (net (code "139") (name "unconnected-(U1-IO32-Pad8)") (class "Default")
      (node (ref "U1") (pin "8") (pinfunction "IO32_8") (pintype "bidirectional"))
    )
    (net (code "140") (name "unconnected-(U1-IO33-Pad9)") (class "Default")
      (node (ref "U1") (pin "9") (pinfunction "IO33_9") (pintype "bidirectional"))
    )
    (net (code "141") (name "unconnected-(U1-IO34-Pad6)") (class "Default")
      (node (ref "U1") (pin "6") (pinfunction "IO34_6") (pintype "bidirectional"))
    )
    (net (code "142") (name "unconnected-(U1-IO35-Pad7)") (class "Default")
      (node (ref "U1") (pin "7") (pinfunction "IO35_7") (pintype "bidirectional"))
    )
    (net (code "143") (name "unconnected-(U1-SCK-Pad20)") (class "Default")
      (node (ref "U1") (pin "20") (pinfunction "SCK_20") (pintype "bidirectional"))
    )
    (net (code "144") (name "unconnected-(U1-SCS-Pad19)") (class "Default")
      (node (ref "U1") (pin "19") (pinfunction "SCS_19") (pintype "bidirectional"))
    )
    (net (code "145") (name "unconnected-(U1-SDI-Pad22)") (class "Default")
      (node (ref "U1") (pin "22") (pinfunction "SDI_22") (pintype "bidirectional"))
    )
    (net (code "146") (name "unconnected-(U1-SDO-Pad21)") (class "Default")
      (node (ref "U1") (pin "21") (pinfunction "SDO_21") (pintype "bidirectional"))
    )
    (net (code "147") (name "unconnected-(U1-SENSOR_VN-Pad5)") (class "Default")
      (node (ref "U1") (pin "5") (pinfunction "SENSOR_VN_5") (pintype "bidirectional"))
    )
    (net (code "148") (name "unconnected-(U1-SENSOR_VP-Pad4)") (class "Default")
      (node (ref "U1") (pin "4") (pinfunction "SENSOR_VP_4") (pintype "bidirectional"))
    )
    (net (code "149") (name "unconnected-(U1-SHD-Pad17)") (class "Default")
      (node (ref "U1") (pin "17") (pinfunction "SHD_17") (pintype "bidirectional"))
    )
    (net (code "150") (name "unconnected-(U1-SWP-Pad18)") (class "Default")
      (node (ref "U1") (pin "18") (pinfunction "SWP_18") (pintype "bidirectional"))
    )
  )
)
